# chess.net
KiCad netlist of a schematic drawn in EAGLE
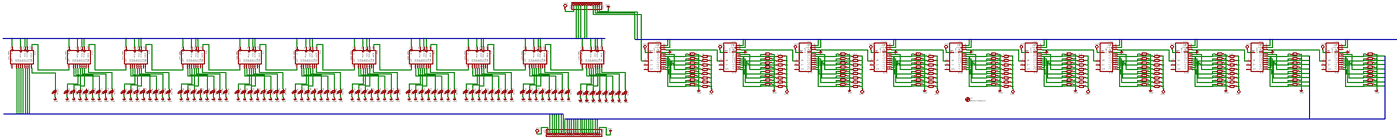
[diagram p0: schematic, sheet 1, overview]
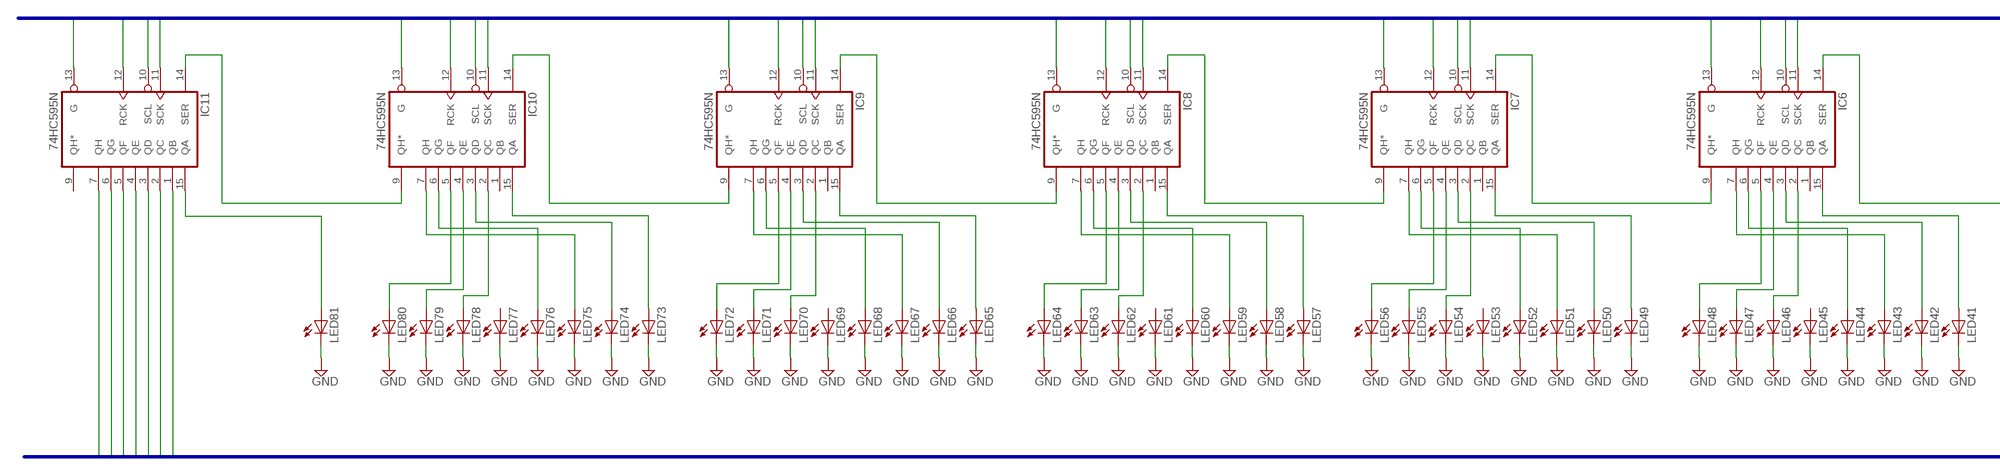
[diagram p1: schematic, sheet 1, part 1 of 4]
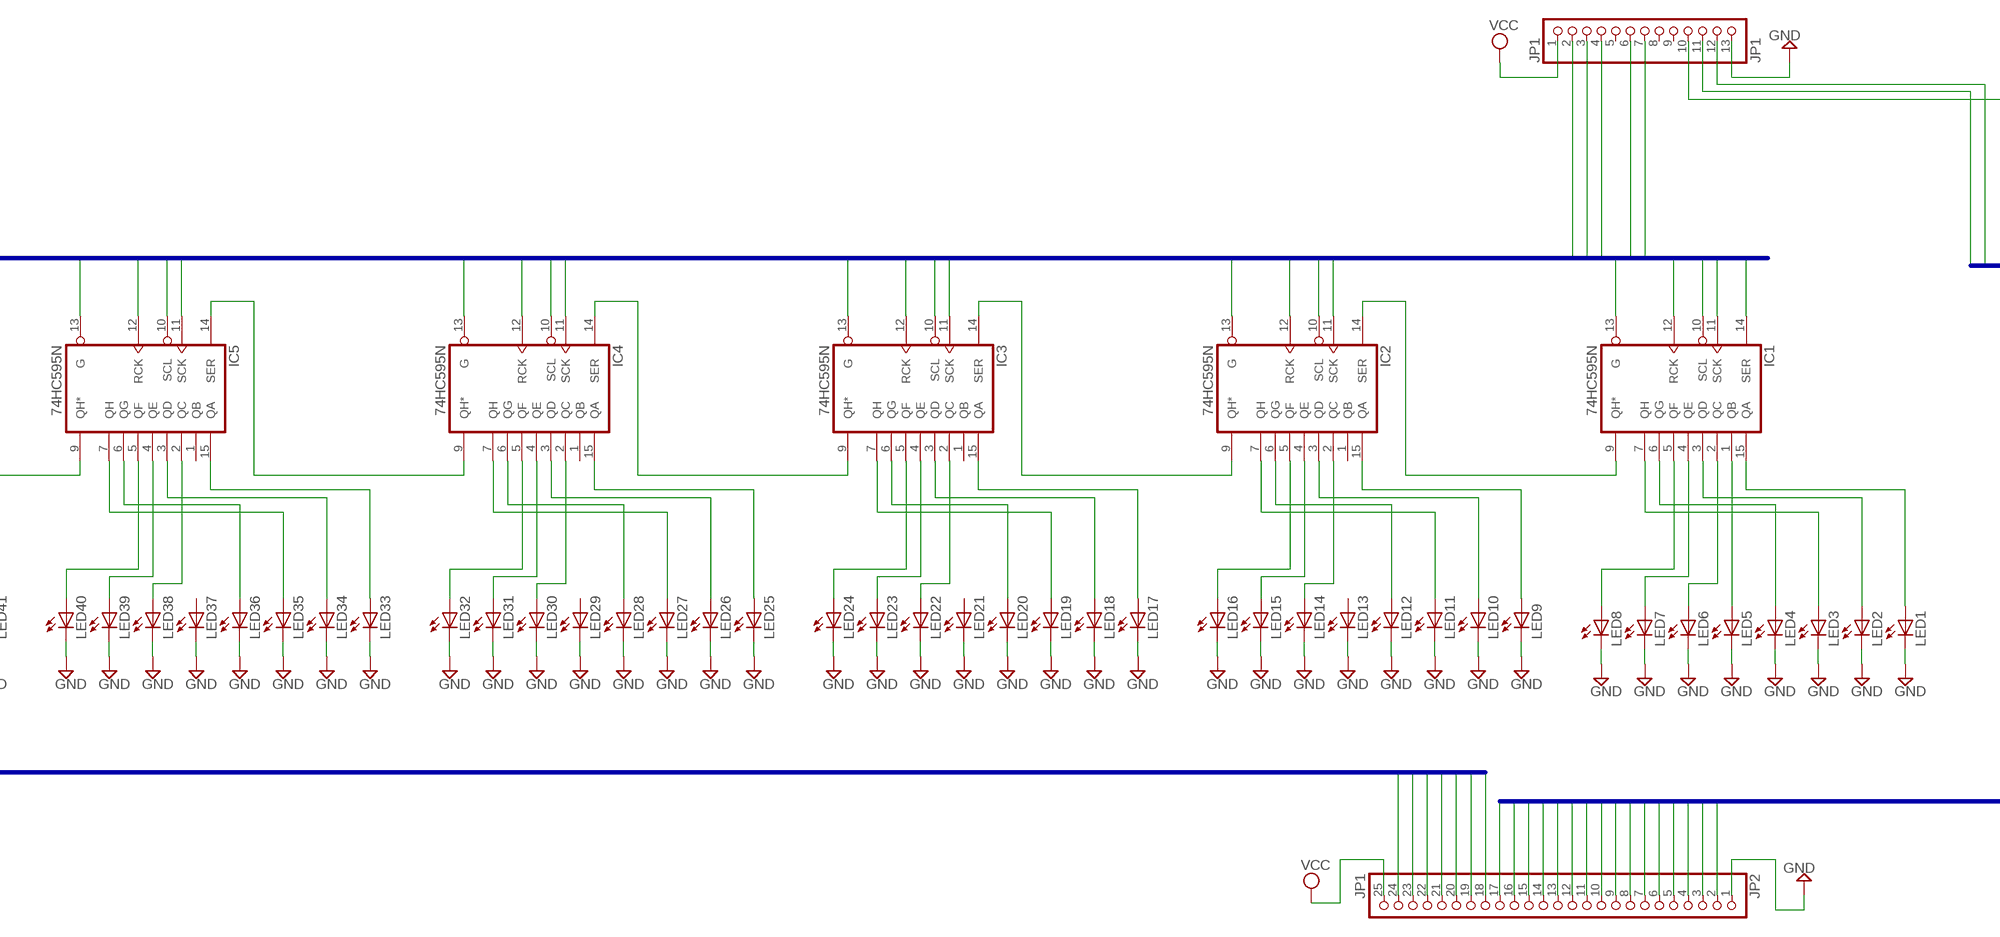
[diagram p2: schematic, sheet 1, part 2 of 4]
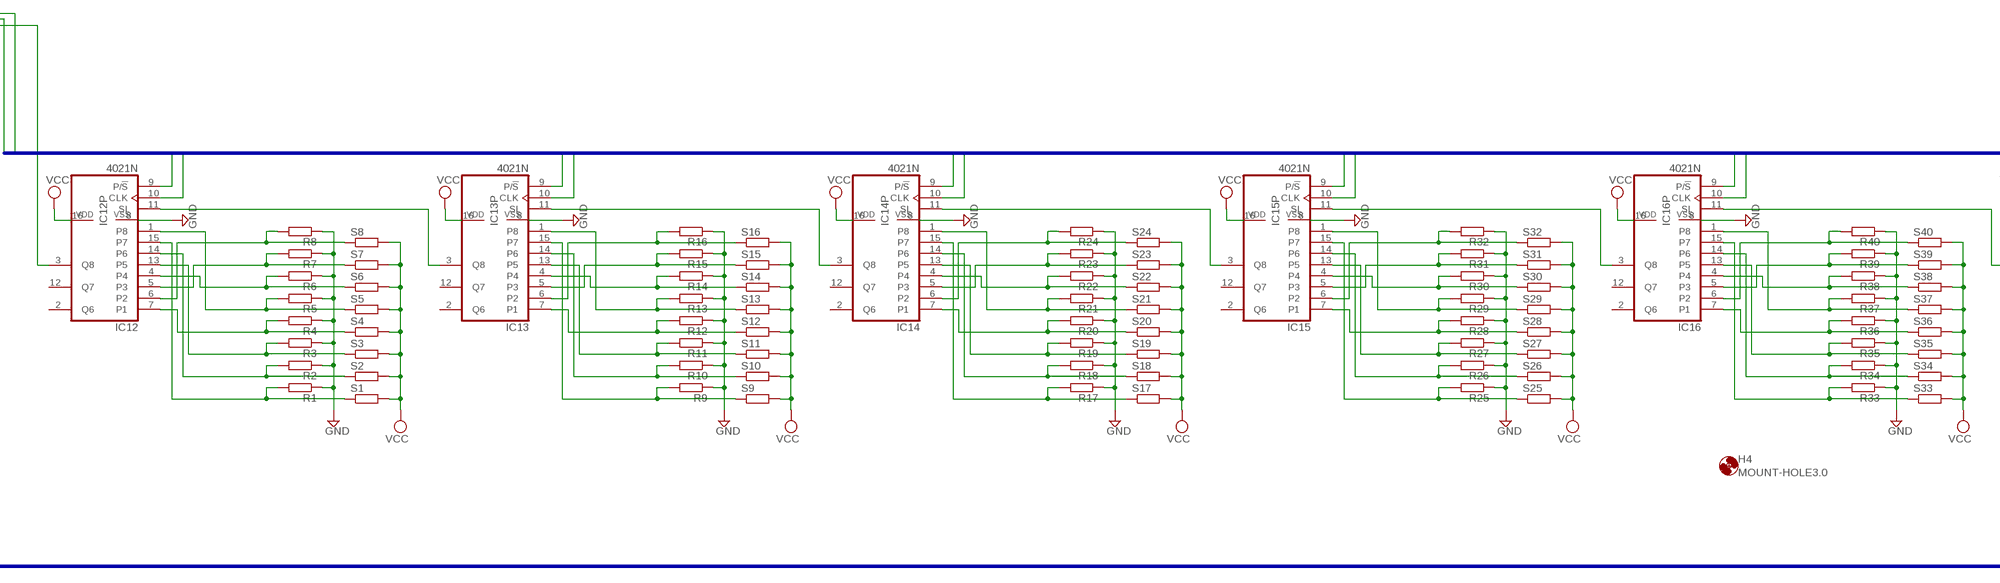
[diagram p3: schematic, sheet 1, part 3 of 4]
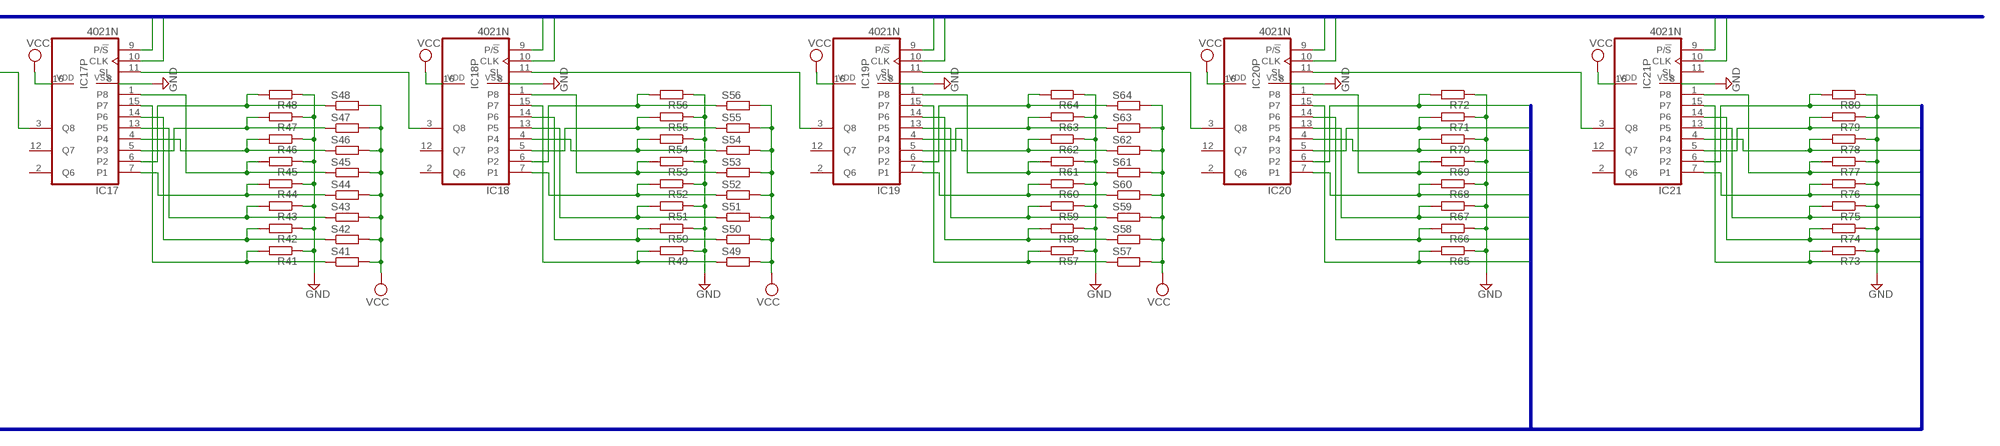
[diagram p4: schematic, sheet 1, part 4 of 4]

(export (version "E")
  (design (tool "Eeschema 10.0.6"))
  (components
    (comp (ref "H4")
      (value "MOUNT-HOLE3.0")
      (footprint "eagle-import:3,0")
      (libsource (lib "eagle-import") (part "MOUNT-HOLE3.0"))
    )
    (comp (ref "IC1")
      (value "74HC595N")
      (footprint "eagle-import:DIL16")
      (libsource (lib "eagle-import") (part "74595NHC"))
    )
    (comp (ref "IC2")
      (value "74HC595N")
      (footprint "eagle-import:DIL16")
      (libsource (lib "eagle-import") (part "74595NHC"))
    )
    (comp (ref "IC3")
      (value "74HC595N")
      (footprint "eagle-import:DIL16")
      (libsource (lib "eagle-import") (part "74595NHC"))
    )
    (comp (ref "IC4")
      (value "74HC595N")
      (footprint "eagle-import:DIL16")
      (libsource (lib "eagle-import") (part "74595NHC"))
    )
    (comp (ref "IC5")
      (value "74HC595N")
      (footprint "eagle-import:DIL16")
      (libsource (lib "eagle-import") (part "74595NHC"))
    )
    (comp (ref "IC6")
      (value "74HC595N")
      (footprint "eagle-import:DIL16")
      (libsource (lib "eagle-import") (part "74595NHC"))
    )
    (comp (ref "IC7")
      (value "74HC595N")
      (footprint "eagle-import:DIL16")
      (libsource (lib "eagle-import") (part "74595NHC"))
    )
    (comp (ref "IC8")
      (value "74HC595N")
      (footprint "eagle-import:DIL16")
      (libsource (lib "eagle-import") (part "74595NHC"))
    )
    (comp (ref "IC9")
      (value "74HC595N")
      (footprint "eagle-import:DIL16")
      (libsource (lib "eagle-import") (part "74595NHC"))
    )
    (comp (ref "IC10")
      (value "74HC595N")
      (footprint "eagle-import:DIL16")
      (libsource (lib "eagle-import") (part "74595NHC"))
    )
    (comp (ref "IC11")
      (value "74HC595N")
      (footprint "eagle-import:DIL16")
      (libsource (lib "eagle-import") (part "74595NHC"))
    )
    (comp (ref "IC12")
      (value "4021N")
      (footprint "eagle-import:DIL16")
      (libsource (lib "eagle-import") (part "4021N"))
    )
    (comp (ref "IC13")
      (value "4021N")
      (footprint "eagle-import:DIL16")
      (libsource (lib "eagle-import") (part "4021N"))
    )
    (comp (ref "IC14")
      (value "4021N")
      (footprint "eagle-import:DIL16")
      (libsource (lib "eagle-import") (part "4021N"))
    )
    (comp (ref "IC15")
      (value "4021N")
      (footprint "eagle-import:DIL16")
      (libsource (lib "eagle-import") (part "4021N"))
    )
    (comp (ref "IC16")
      (value "4021N")
      (footprint "eagle-import:DIL16")
      (libsource (lib "eagle-import") (part "4021N"))
    )
    (comp (ref "IC17")
      (value "4021N")
      (footprint "eagle-import:DIL16")
      (libsource (lib "eagle-import") (part "4021N"))
    )
    (comp (ref "IC18")
      (value "4021N")
      (footprint "eagle-import:DIL16")
      (libsource (lib "eagle-import") (part "4021N"))
    )
    (comp (ref "IC19")
      (value "4021N")
      (footprint "eagle-import:DIL16")
      (libsource (lib "eagle-import") (part "4021N"))
    )
    (comp (ref "IC20")
      (value "4021N")
      (footprint "eagle-import:DIL16")
      (libsource (lib "eagle-import") (part "4021N"))
    )
    (comp (ref "IC21")
      (value "4021N")
      (footprint "eagle-import:DIL16")
      (libsource (lib "eagle-import") (part "4021N"))
    )
    (comp (ref "JP1")
      (value "JP1")
      (footprint "eagle-import:1X13")
      (libsource (lib "eagle-import") (part "PINHD-1X13"))
    )
    (comp (ref "JP2")
      (value "JP1")
      (footprint "eagle-import:1X25")
      (libsource (lib "eagle-import") (part "PINHD-1X25"))
    )
    (comp (ref "LED1")
      (value "LED5MM")
      (footprint "eagle-import:LED5MM")
      (libsource (lib "eagle-import") (part "LED5MM"))
    )
    (comp (ref "LED2")
      (value "LED5MM")
      (footprint "eagle-import:LED5MM")
      (libsource (lib "eagle-import") (part "LED5MM"))
    )
    (comp (ref "LED3")
      (value "LED5MM")
      (footprint "eagle-import:LED5MM")
      (libsource (lib "eagle-import") (part "LED5MM"))
    )
    (comp (ref "LED4")
      (value "LED5MM")
      (footprint "eagle-import:LED5MM")
      (libsource (lib "eagle-import") (part "LED5MM"))
    )
    (comp (ref "LED5")
      (value "LED5MM")
      (footprint "eagle-import:LED5MM")
      (libsource (lib "eagle-import") (part "LED5MM"))
    )
    (comp (ref "LED6")
      (value "LED5MM")
      (footprint "eagle-import:LED5MM")
      (libsource (lib "eagle-import") (part "LED5MM"))
    )
    (comp (ref "LED7")
      (value "LED5MM")
      (footprint "eagle-import:LED5MM")
      (libsource (lib "eagle-import") (part "LED5MM"))
    )
    (comp (ref "LED8")
      (value "LED5MM")
      (footprint "eagle-import:LED5MM")
      (libsource (lib "eagle-import") (part "LED5MM"))
    )
    (comp (ref "LED9")
      (value "LED5MM")
      (footprint "eagle-import:LED5MM")
      (libsource (lib "eagle-import") (part "LED5MM"))
    )
    (comp (ref "LED10")
      (value "LED5MM")
      (footprint "eagle-import:LED5MM")
      (libsource (lib "eagle-import") (part "LED5MM"))
    )
    (comp (ref "LED11")
      (value "LED5MM")
      (footprint "eagle-import:LED5MM")
      (libsource (lib "eagle-import") (part "LED5MM"))
    )
    (comp (ref "LED12")
      (value "LED5MM")
      (footprint "eagle-import:LED5MM")
      (libsource (lib "eagle-import") (part "LED5MM"))
    )
    (comp (ref "LED13")
      (value "LED5MM")
      (footprint "eagle-import:LED5MM")
      (libsource (lib "eagle-import") (part "LED5MM"))
    )
    (comp (ref "LED14")
      (value "LED5MM")
      (footprint "eagle-import:LED5MM")
      (libsource (lib "eagle-import") (part "LED5MM"))
    )
    (comp (ref "LED15")
      (value "LED5MM")
      (footprint "eagle-import:LED5MM")
      (libsource (lib "eagle-import") (part "LED5MM"))
    )
    (comp (ref "LED16")
      (value "LED5MM")
      (footprint "eagle-import:LED5MM")
      (libsource (lib "eagle-import") (part "LED5MM"))
    )
    (comp (ref "LED17")
      (value "LED5MM")
      (footprint "eagle-import:LED5MM")
      (libsource (lib "eagle-import") (part "LED5MM"))
    )
    (comp (ref "LED18")
      (value "LED5MM")
      (footprint "eagle-import:LED5MM")
      (libsource (lib "eagle-import") (part "LED5MM"))
    )
    (comp (ref "LED19")
      (value "LED5MM")
      (footprint "eagle-import:LED5MM")
      (libsource (lib "eagle-import") (part "LED5MM"))
    )
    (comp (ref "LED20")
      (value "LED5MM")
      (footprint "eagle-import:LED5MM")
      (libsource (lib "eagle-import") (part "LED5MM"))
    )
    (comp (ref "LED21")
      (value "LED5MM")
      (footprint "eagle-import:LED5MM")
      (libsource (lib "eagle-import") (part "LED5MM"))
    )
    (comp (ref "LED22")
      (value "LED5MM")
      (footprint "eagle-import:LED5MM")
      (libsource (lib "eagle-import") (part "LED5MM"))
    )
    (comp (ref "LED23")
      (value "LED5MM")
      (footprint "eagle-import:LED5MM")
      (libsource (lib "eagle-import") (part "LED5MM"))
    )
    (comp (ref "LED24")
      (value "LED5MM")
      (footprint "eagle-import:LED5MM")
      (libsource (lib "eagle-import") (part "LED5MM"))
    )
    (comp (ref "LED25")
      (value "LED5MM")
      (footprint "eagle-import:LED5MM")
      (libsource (lib "eagle-import") (part "LED5MM"))
    )
    (comp (ref "LED26")
      (value "LED5MM")
      (footprint "eagle-import:LED5MM")
      (libsource (lib "eagle-import") (part "LED5MM"))
    )
    (comp (ref "LED27")
      (value "LED5MM")
      (footprint "eagle-import:LED5MM")
      (libsource (lib "eagle-import") (part "LED5MM"))
    )
    (comp (ref "LED28")
      (value "LED5MM")
      (footprint "eagle-import:LED5MM")
      (libsource (lib "eagle-import") (part "LED5MM"))
    )
    (comp (ref "LED29")
      (value "LED5MM")
      (footprint "eagle-import:LED5MM")
      (libsource (lib "eagle-import") (part "LED5MM"))
    )
    (comp (ref "LED30")
      (value "LED5MM")
      (footprint "eagle-import:LED5MM")
      (libsource (lib "eagle-import") (part "LED5MM"))
    )
    (comp (ref "LED31")
      (value "LED5MM")
      (footprint "eagle-import:LED5MM")
      (libsource (lib "eagle-import") (part "LED5MM"))
    )
    (comp (ref "LED32")
      (value "LED5MM")
      (footprint "eagle-import:LED5MM")
      (libsource (lib "eagle-import") (part "LED5MM"))
    )
    (comp (ref "LED33")
      (value "LED5MM")
      (footprint "eagle-import:LED5MM")
      (libsource (lib "eagle-import") (part "LED5MM"))
    )
    (comp (ref "LED34")
      (value "LED5MM")
      (footprint "eagle-import:LED5MM")
      (libsource (lib "eagle-import") (part "LED5MM"))
    )
    (comp (ref "LED35")
      (value "LED5MM")
      (footprint "eagle-import:LED5MM")
      (libsource (lib "eagle-import") (part "LED5MM"))
    )
    (comp (ref "LED36")
      (value "LED5MM")
      (footprint "eagle-import:LED5MM")
      (libsource (lib "eagle-import") (part "LED5MM"))
    )
    (comp (ref "LED37")
      (value "LED5MM")
      (footprint "eagle-import:LED5MM")
      (libsource (lib "eagle-import") (part "LED5MM"))
    )
    (comp (ref "LED38")
      (value "LED5MM")
      (footprint "eagle-import:LED5MM")
      (libsource (lib "eagle-import") (part "LED5MM"))
    )
    (comp (ref "LED39")
      (value "LED5MM")
      (footprint "eagle-import:LED5MM")
      (libsource (lib "eagle-import") (part "LED5MM"))
    )
    (comp (ref "LED40")
      (value "LED5MM")
      (footprint "eagle-import:LED5MM")
      (libsource (lib "eagle-import") (part "LED5MM"))
    )
    (comp (ref "LED41")
      (value "LED5MM")
      (footprint "eagle-import:LED5MM")
      (libsource (lib "eagle-import") (part "LED5MM"))
    )
    (comp (ref "LED42")
      (value "LED5MM")
      (footprint "eagle-import:LED5MM")
      (libsource (lib "eagle-import") (part "LED5MM"))
    )
    (comp (ref "LED43")
      (value "LED5MM")
      (footprint "eagle-import:LED5MM")
      (libsource (lib "eagle-import") (part "LED5MM"))
    )
    (comp (ref "LED44")
      (value "LED5MM")
      (footprint "eagle-import:LED5MM")
      (libsource (lib "eagle-import") (part "LED5MM"))
    )
    (comp (ref "LED45")
      (value "LED5MM")
      (footprint "eagle-import:LED5MM")
      (libsource (lib "eagle-import") (part "LED5MM"))
    )
    (comp (ref "LED46")
      (value "LED5MM")
      (footprint "eagle-import:LED5MM")
      (libsource (lib "eagle-import") (part "LED5MM"))
    )
    (comp (ref "LED47")
      (value "LED5MM")
      (footprint "eagle-import:LED5MM")
      (libsource (lib "eagle-import") (part "LED5MM"))
    )
    (comp (ref "LED48")
      (value "LED5MM")
      (footprint "eagle-import:LED5MM")
      (libsource (lib "eagle-import") (part "LED5MM"))
    )
    (comp (ref "LED49")
      (value "LED5MM")
      (footprint "eagle-import:LED5MM")
      (libsource (lib "eagle-import") (part "LED5MM"))
    )
    (comp (ref "LED50")
      (value "LED5MM")
      (footprint "eagle-import:LED5MM")
      (libsource (lib "eagle-import") (part "LED5MM"))
    )
    (comp (ref "LED51")
      (value "LED5MM")
      (footprint "eagle-import:LED5MM")
      (libsource (lib "eagle-import") (part "LED5MM"))
    )
    (comp (ref "LED52")
      (value "LED5MM")
      (footprint "eagle-import:LED5MM")
      (libsource (lib "eagle-import") (part "LED5MM"))
    )
    (comp (ref "LED53")
      (value "LED5MM")
      (footprint "eagle-import:LED5MM")
      (libsource (lib "eagle-import") (part "LED5MM"))
    )
    (comp (ref "LED54")
      (value "LED5MM")
      (footprint "eagle-import:LED5MM")
      (libsource (lib "eagle-import") (part "LED5MM"))
    )
    (comp (ref "LED55")
      (value "LED5MM")
      (footprint "eagle-import:LED5MM")
      (libsource (lib "eagle-import") (part "LED5MM"))
    )
    (comp (ref "LED56")
      (value "LED5MM")
      (footprint "eagle-import:LED5MM")
      (libsource (lib "eagle-import") (part "LED5MM"))
    )
    (comp (ref "LED57")
      (value "LED5MM")
      (footprint "eagle-import:LED5MM")
      (libsource (lib "eagle-import") (part "LED5MM"))
    )
    (comp (ref "LED58")
      (value "LED5MM")
      (footprint "eagle-import:LED5MM")
      (libsource (lib "eagle-import") (part "LED5MM"))
    )
    (comp (ref "LED59")
      (value "LED5MM")
      (footprint "eagle-import:LED5MM")
      (libsource (lib "eagle-import") (part "LED5MM"))
    )
    (comp (ref "LED60")
      (value "LED5MM")
      (footprint "eagle-import:LED5MM")
      (libsource (lib "eagle-import") (part "LED5MM"))
    )
    (comp (ref "LED61")
      (value "LED5MM")
      (footprint "eagle-import:LED5MM")
      (libsource (lib "eagle-import") (part "LED5MM"))
    )
    (comp (ref "LED62")
      (value "LED5MM")
      (footprint "eagle-import:LED5MM")
      (libsource (lib "eagle-import") (part "LED5MM"))
    )
    (comp (ref "LED63")
      (value "LED5MM")
      (footprint "eagle-import:LED5MM")
      (libsource (lib "eagle-import") (part "LED5MM"))
    )
    (comp (ref "LED64")
      (value "LED5MM")
      (footprint "eagle-import:LED5MM")
      (libsource (lib "eagle-import") (part "LED5MM"))
    )
    (comp (ref "LED65")
      (value "LED5MM")
      (footprint "eagle-import:LED5MM")
      (libsource (lib "eagle-import") (part "LED5MM"))
    )
    (comp (ref "LED66")
      (value "LED5MM")
      (footprint "eagle-import:LED5MM")
      (libsource (lib "eagle-import") (part "LED5MM"))
    )
    (comp (ref "LED67")
      (value "LED5MM")
      (footprint "eagle-import:LED5MM")
      (libsource (lib "eagle-import") (part "LED5MM"))
    )
    (comp (ref "LED68")
      (value "LED5MM")
      (footprint "eagle-import:LED5MM")
      (libsource (lib "eagle-import") (part "LED5MM"))
    )
    (comp (ref "LED69")
      (value "LED5MM")
      (footprint "eagle-import:LED5MM")
      (libsource (lib "eagle-import") (part "LED5MM"))
    )
    (comp (ref "LED70")
      (value "LED5MM")
      (footprint "eagle-import:LED5MM")
      (libsource (lib "eagle-import") (part "LED5MM"))
    )
    (comp (ref "LED71")
      (value "LED5MM")
      (footprint "eagle-import:LED5MM")
      (libsource (lib "eagle-import") (part "LED5MM"))
    )
    (comp (ref "LED72")
      (value "LED5MM")
      (footprint "eagle-import:LED5MM")
      (libsource (lib "eagle-import") (part "LED5MM"))
    )
    (comp (ref "LED73")
      (value "LED5MM")
      (footprint "eagle-import:LED5MM")
      (libsource (lib "eagle-import") (part "LED5MM"))
    )
    (comp (ref "LED74")
      (value "LED5MM")
      (footprint "eagle-import:LED5MM")
      (libsource (lib "eagle-import") (part "LED5MM"))
    )
    (comp (ref "LED75")
      (value "LED5MM")
      (footprint "eagle-import:LED5MM")
      (libsource (lib "eagle-import") (part "LED5MM"))
    )
    (comp (ref "LED76")
      (value "LED5MM")
      (footprint "eagle-import:LED5MM")
      (libsource (lib "eagle-import") (part "LED5MM"))
    )
    (comp (ref "LED77")
      (value "LED5MM")
      (footprint "eagle-import:LED5MM")
      (libsource (lib "eagle-import") (part "LED5MM"))
    )
    (comp (ref "LED78")
      (value "LED5MM")
      (footprint "eagle-import:LED5MM")
      (libsource (lib "eagle-import") (part "LED5MM"))
    )
    (comp (ref "LED79")
      (value "LED5MM")
      (footprint "eagle-import:LED5MM")
      (libsource (lib "eagle-import") (part "LED5MM"))
    )
    (comp (ref "LED80")
      (value "LED5MM")
      (footprint "eagle-import:LED5MM")
      (libsource (lib "eagle-import") (part "LED5MM"))
    )
    (comp (ref "LED81")
      (value "LED5MM")
      (footprint "eagle-import:LED5MM")
      (libsource (lib "eagle-import") (part "LED5MM"))
    )
    (comp (ref "R1")
      (value "R-EU_0207/15")
      (footprint "eagle-import:0207_15")
      (libsource (lib "eagle-import") (part "R-EU_0207/15"))
    )
    (comp (ref "R2")
      (value "R-EU_0207/15")
      (footprint "eagle-import:0207_15")
      (libsource (lib "eagle-import") (part "R-EU_0207/15"))
    )
    (comp (ref "R3")
      (value "R-EU_0207/15")
      (footprint "eagle-import:0207_15")
      (libsource (lib "eagle-import") (part "R-EU_0207/15"))
    )
    (comp (ref "R4")
      (value "R-EU_0207/15")
      (footprint "eagle-import:0207_15")
      (libsource (lib "eagle-import") (part "R-EU_0207/15"))
    )
    (comp (ref "R5")
      (value "R-EU_0207/15")
      (footprint "eagle-import:0207_15")
      (libsource (lib "eagle-import") (part "R-EU_0207/15"))
    )
    (comp (ref "R6")
      (value "R-EU_0207/15")
      (footprint "eagle-import:0207_15")
      (libsource (lib "eagle-import") (part "R-EU_0207/15"))
    )
    (comp (ref "R7")
      (value "R-EU_0207/15")
      (footprint "eagle-import:0207_15")
      (libsource (lib "eagle-import") (part "R-EU_0207/15"))
    )
    (comp (ref "R8")
      (value "R-EU_0207/15")
      (footprint "eagle-import:0207_15")
      (libsource (lib "eagle-import") (part "R-EU_0207/15"))
    )
    (comp (ref "R9")
      (value "R-EU_0207/15")
      (footprint "eagle-import:0207_15")
      (libsource (lib "eagle-import") (part "R-EU_0207/15"))
    )
    (comp (ref "R10")
      (value "R-EU_0207/15")
      (footprint "eagle-import:0207_15")
      (libsource (lib "eagle-import") (part "R-EU_0207/15"))
    )
    (comp (ref "R11")
      (value "R-EU_0207/15")
      (footprint "eagle-import:0207_15")
      (libsource (lib "eagle-import") (part "R-EU_0207/15"))
    )
    (comp (ref "R12")
      (value "R-EU_0207/15")
      (footprint "eagle-import:0207_15")
      (libsource (lib "eagle-import") (part "R-EU_0207/15"))
    )
    (comp (ref "R13")
      (value "R-EU_0207/15")
      (footprint "eagle-import:0207_15")
      (libsource (lib "eagle-import") (part "R-EU_0207/15"))
    )
    (comp (ref "R14")
      (value "R-EU_0207/15")
      (footprint "eagle-import:0207_15")
      (libsource (lib "eagle-import") (part "R-EU_0207/15"))
    )
    (comp (ref "R15")
      (value "R-EU_0207/15")
      (footprint "eagle-import:0207_15")
      (libsource (lib "eagle-import") (part "R-EU_0207/15"))
    )
    (comp (ref "R16")
      (value "R-EU_0207/15")
      (footprint "eagle-import:0207_15")
      (libsource (lib "eagle-import") (part "R-EU_0207/15"))
    )
    (comp (ref "R17")
      (value "R-EU_0207/15")
      (footprint "eagle-import:0207_15")
      (libsource (lib "eagle-import") (part "R-EU_0207/15"))
    )
    (comp (ref "R18")
      (value "R-EU_0207/15")
      (footprint "eagle-import:0207_15")
      (libsource (lib "eagle-import") (part "R-EU_0207/15"))
    )
    (comp (ref "R19")
      (value "R-EU_0207/15")
      (footprint "eagle-import:0207_15")
      (libsource (lib "eagle-import") (part "R-EU_0207/15"))
    )
    (comp (ref "R20")
      (value "R-EU_0207/15")
      (footprint "eagle-import:0207_15")
      (libsource (lib "eagle-import") (part "R-EU_0207/15"))
    )
    (comp (ref "R21")
      (value "R-EU_0207/15")
      (footprint "eagle-import:0207_15")
      (libsource (lib "eagle-import") (part "R-EU_0207/15"))
    )
    (comp (ref "R22")
      (value "R-EU_0207/15")
      (footprint "eagle-import:0207_15")
      (libsource (lib "eagle-import") (part "R-EU_0207/15"))
    )
    (comp (ref "R23")
      (value "R-EU_0207/15")
      (footprint "eagle-import:0207_15")
      (libsource (lib "eagle-import") (part "R-EU_0207/15"))
    )
    (comp (ref "R24")
      (value "R-EU_0207/15")
      (footprint "eagle-import:0207_15")
      (libsource (lib "eagle-import") (part "R-EU_0207/15"))
    )
    (comp (ref "R25")
      (value "R-EU_0207/15")
      (footprint "eagle-import:0207_15")
      (libsource (lib "eagle-import") (part "R-EU_0207/15"))
    )
    (comp (ref "R26")
      (value "R-EU_0207/15")
      (footprint "eagle-import:0207_15")
      (libsource (lib "eagle-import") (part "R-EU_0207/15"))
    )
    (comp (ref "R27")
      (value "R-EU_0207/15")
      (footprint "eagle-import:0207_15")
      (libsource (lib "eagle-import") (part "R-EU_0207/15"))
    )
    (comp (ref "R28")
      (value "R-EU_0207/15")
      (footprint "eagle-import:0207_15")
      (libsource (lib "eagle-import") (part "R-EU_0207/15"))
    )
    (comp (ref "R29")
      (value "R-EU_0207/15")
      (footprint "eagle-import:0207_15")
      (libsource (lib "eagle-import") (part "R-EU_0207/15"))
    )
    (comp (ref "R30")
      (value "R-EU_0207/15")
      (footprint "eagle-import:0207_15")
      (libsource (lib "eagle-import") (part "R-EU_0207/15"))
    )
    (comp (ref "R31")
      (value "R-EU_0207/15")
      (footprint "eagle-import:0207_15")
      (libsource (lib "eagle-import") (part "R-EU_0207/15"))
    )
    (comp (ref "R32")
      (value "R-EU_0207/15")
      (footprint "eagle-import:0207_15")
      (libsource (lib "eagle-import") (part "R-EU_0207/15"))
    )
    (comp (ref "R33")
      (value "R-EU_0207/15")
      (footprint "eagle-import:0207_15")
      (libsource (lib "eagle-import") (part "R-EU_0207/15"))
    )
    (comp (ref "R34")
      (value "R-EU_0207/15")
      (footprint "eagle-import:0207_15")
      (libsource (lib "eagle-import") (part "R-EU_0207/15"))
    )
    (comp (ref "R35")
      (value "R-EU_0207/15")
      (footprint "eagle-import:0207_15")
      (libsource (lib "eagle-import") (part "R-EU_0207/15"))
    )
    (comp (ref "R36")
      (value "R-EU_0207/15")
      (footprint "eagle-import:0207_15")
      (libsource (lib "eagle-import") (part "R-EU_0207/15"))
    )
    (comp (ref "R37")
      (value "R-EU_0207/15")
      (footprint "eagle-import:0207_15")
      (libsource (lib "eagle-import") (part "R-EU_0207/15"))
    )
    (comp (ref "R38")
      (value "R-EU_0207/15")
      (footprint "eagle-import:0207_15")
      (libsource (lib "eagle-import") (part "R-EU_0207/15"))
    )
    (comp (ref "R39")
      (value "R-EU_0207/15")
      (footprint "eagle-import:0207_15")
      (libsource (lib "eagle-import") (part "R-EU_0207/15"))
    )
    (comp (ref "R40")
      (value "R-EU_0207/15")
      (footprint "eagle-import:0207_15")
      (libsource (lib "eagle-import") (part "R-EU_0207/15"))
    )
    (comp (ref "R41")
      (value "R-EU_0207/15")
      (footprint "eagle-import:0207_15")
      (libsource (lib "eagle-import") (part "R-EU_0207/15"))
    )
    (comp (ref "R42")
      (value "R-EU_0207/15")
      (footprint "eagle-import:0207_15")
      (libsource (lib "eagle-import") (part "R-EU_0207/15"))
    )
    (comp (ref "R43")
      (value "R-EU_0207/15")
      (footprint "eagle-import:0207_15")
      (libsource (lib "eagle-import") (part "R-EU_0207/15"))
    )
    (comp (ref "R44")
      (value "R-EU_0207/15")
      (footprint "eagle-import:0207_15")
      (libsource (lib "eagle-import") (part "R-EU_0207/15"))
    )
    (comp (ref "R45")
      (value "R-EU_0207/15")
      (footprint "eagle-import:0207_15")
      (libsource (lib "eagle-import") (part "R-EU_0207/15"))
    )
    (comp (ref "R46")
      (value "R-EU_0207/15")
      (footprint "eagle-import:0207_15")
      (libsource (lib "eagle-import") (part "R-EU_0207/15"))
    )
    (comp (ref "R47")
      (value "R-EU_0207/15")
      (footprint "eagle-import:0207_15")
      (libsource (lib "eagle-import") (part "R-EU_0207/15"))
    )
    (comp (ref "R48")
      (value "R-EU_0207/15")
      (footprint "eagle-import:0207_15")
      (libsource (lib "eagle-import") (part "R-EU_0207/15"))
    )
    (comp (ref "R49")
      (value "R-EU_0207/15")
      (footprint "eagle-import:0207_15")
      (libsource (lib "eagle-import") (part "R-EU_0207/15"))
    )
    (comp (ref "R50")
      (value "R-EU_0207/15")
      (footprint "eagle-import:0207_15")
      (libsource (lib "eagle-import") (part "R-EU_0207/15"))
    )
    (comp (ref "R51")
      (value "R-EU_0207/15")
      (footprint "eagle-import:0207_15")
      (libsource (lib "eagle-import") (part "R-EU_0207/15"))
    )
    (comp (ref "R52")
      (value "R-EU_0207/15")
      (footprint "eagle-import:0207_15")
      (libsource (lib "eagle-import") (part "R-EU_0207/15"))
    )
    (comp (ref "R53")
      (value "R-EU_0207/15")
      (footprint "eagle-import:0207_15")
      (libsource (lib "eagle-import") (part "R-EU_0207/15"))
    )
    (comp (ref "R54")
      (value "R-EU_0207/15")
      (footprint "eagle-import:0207_15")
      (libsource (lib "eagle-import") (part "R-EU_0207/15"))
    )
    (comp (ref "R55")
      (value "R-EU_0207/15")
      (footprint "eagle-import:0207_15")
      (libsource (lib "eagle-import") (part "R-EU_0207/15"))
    )
    (comp (ref "R56")
      (value "R-EU_0207/15")
      (footprint "eagle-import:0207_15")
      (libsource (lib "eagle-import") (part "R-EU_0207/15"))
    )
    (comp (ref "R57")
      (value "R-EU_0207/15")
      (footprint "eagle-import:0207_15")
      (libsource (lib "eagle-import") (part "R-EU_0207/15"))
    )
    (comp (ref "R58")
      (value "R-EU_0207/15")
      (footprint "eagle-import:0207_15")
      (libsource (lib "eagle-import") (part "R-EU_0207/15"))
    )
    (comp (ref "R59")
      (value "R-EU_0207/15")
      (footprint "eagle-import:0207_15")
      (libsource (lib "eagle-import") (part "R-EU_0207/15"))
    )
    (comp (ref "R60")
      (value "R-EU_0207/15")
      (footprint "eagle-import:0207_15")
      (libsource (lib "eagle-import") (part "R-EU_0207/15"))
    )
    (comp (ref "R61")
      (value "R-EU_0207/15")
      (footprint "eagle-import:0207_15")
      (libsource (lib "eagle-import") (part "R-EU_0207/15"))
    )
    (comp (ref "R62")
      (value "R-EU_0207/15")
      (footprint "eagle-import:0207_15")
      (libsource (lib "eagle-import") (part "R-EU_0207/15"))
    )
    (comp (ref "R63")
      (value "R-EU_0207/15")
      (footprint "eagle-import:0207_15")
      (libsource (lib "eagle-import") (part "R-EU_0207/15"))
    )
    (comp (ref "R64")
      (value "R-EU_0207/15")
      (footprint "eagle-import:0207_15")
      (libsource (lib "eagle-import") (part "R-EU_0207/15"))
    )
    (comp (ref "R65")
      (value "R-EU_0207/15")
      (footprint "eagle-import:0207_15")
      (libsource (lib "eagle-import") (part "R-EU_0207/15"))
    )
    (comp (ref "R66")
      (value "R-EU_0207/15")
      (footprint "eagle-import:0207_15")
      (libsource (lib "eagle-import") (part "R-EU_0207/15"))
    )
    (comp (ref "R67")
      (value "R-EU_0207/15")
      (footprint "eagle-import:0207_15")
      (libsource (lib "eagle-import") (part "R-EU_0207/15"))
    )
    (comp (ref "R68")
      (value "R-EU_0207/15")
      (footprint "eagle-import:0207_15")
      (libsource (lib "eagle-import") (part "R-EU_0207/15"))
    )
    (comp (ref "R69")
      (value "R-EU_0207/15")
      (footprint "eagle-import:0207_15")
      (libsource (lib "eagle-import") (part "R-EU_0207/15"))
    )
    (comp (ref "R70")
      (value "R-EU_0207/15")
      (footprint "eagle-import:0207_15")
      (libsource (lib "eagle-import") (part "R-EU_0207/15"))
    )
    (comp (ref "R71")
      (value "R-EU_0207/15")
      (footprint "eagle-import:0207_15")
      (libsource (lib "eagle-import") (part "R-EU_0207/15"))
    )
    (comp (ref "R72")
      (value "R-EU_0207/15")
      (footprint "eagle-import:0207_15")
      (libsource (lib "eagle-import") (part "R-EU_0207/15"))
    )
    (comp (ref "R73")
      (value "R-EU_0207/15")
      (footprint "eagle-import:0207_15")
      (libsource (lib "eagle-import") (part "R-EU_0207/15"))
    )
    (comp (ref "R74")
      (value "R-EU_0207/15")
      (footprint "eagle-import:0207_15")
      (libsource (lib "eagle-import") (part "R-EU_0207/15"))
    )
    (comp (ref "R75")
      (value "R-EU_0207/15")
      (footprint "eagle-import:0207_15")
      (libsource (lib "eagle-import") (part "R-EU_0207/15"))
    )
    (comp (ref "R76")
      (value "R-EU_0207/15")
      (footprint "eagle-import:0207_15")
      (libsource (lib "eagle-import") (part "R-EU_0207/15"))
    )
    (comp (ref "R77")
      (value "R-EU_0207/15")
      (footprint "eagle-import:0207_15")
      (libsource (lib "eagle-import") (part "R-EU_0207/15"))
    )
    (comp (ref "R78")
      (value "R-EU_0207/15")
      (footprint "eagle-import:0207_15")
      (libsource (lib "eagle-import") (part "R-EU_0207/15"))
    )
    (comp (ref "R79")
      (value "R-EU_0207/15")
      (footprint "eagle-import:0207_15")
      (libsource (lib "eagle-import") (part "R-EU_0207/15"))
    )
    (comp (ref "R80")
      (value "R-EU_0207/15")
      (footprint "eagle-import:0207_15")
      (libsource (lib "eagle-import") (part "R-EU_0207/15"))
    )
    (comp (ref "S1")
      (value "R-EU_0617/22")
      (footprint "eagle-import:0617_22")
      (libsource (lib "eagle-import") (part "R-EU_0617/22"))
    )
    (comp (ref "S2")
      (value "R-EU_0617/22")
      (footprint "eagle-import:0617_22")
      (libsource (lib "eagle-import") (part "R-EU_0617/22"))
    )
    (comp (ref "S3")
      (value "R-EU_0617/22")
      (footprint "eagle-import:0617_22")
      (libsource (lib "eagle-import") (part "R-EU_0617/22"))
    )
    (comp (ref "S4")
      (value "R-EU_0617/22")
      (footprint "eagle-import:0617_22")
      (libsource (lib "eagle-import") (part "R-EU_0617/22"))
    )
    (comp (ref "S5")
      (value "R-EU_0617/22")
      (footprint "eagle-import:0617_22")
      (libsource (lib "eagle-import") (part "R-EU_0617/22"))
    )
    (comp (ref "S6")
      (value "R-EU_0617/22")
      (footprint "eagle-import:0617_22")
      (libsource (lib "eagle-import") (part "R-EU_0617/22"))
    )
    (comp (ref "S7")
      (value "R-EU_0617/22")
      (footprint "eagle-import:0617_22")
      (libsource (lib "eagle-import") (part "R-EU_0617/22"))
    )
    (comp (ref "S8")
      (value "R-EU_0617/22")
      (footprint "eagle-import:0617_22")
      (libsource (lib "eagle-import") (part "R-EU_0617/22"))
    )
    (comp (ref "S9")
      (value "R-EU_0617/22")
      (footprint "eagle-import:0617_22")
      (libsource (lib "eagle-import") (part "R-EU_0617/22"))
    )
    (comp (ref "S10")
      (value "R-EU_0617/22")
      (footprint "eagle-import:0617_22")
      (libsource (lib "eagle-import") (part "R-EU_0617/22"))
    )
    (comp (ref "S11")
      (value "R-EU_0617/22")
      (footprint "eagle-import:0617_22")
      (libsource (lib "eagle-import") (part "R-EU_0617/22"))
    )
    (comp (ref "S12")
      (value "R-EU_0617/22")
      (footprint "eagle-import:0617_22")
      (libsource (lib "eagle-import") (part "R-EU_0617/22"))
    )
    (comp (ref "S13")
      (value "R-EU_0617/22")
      (footprint "eagle-import:0617_22")
      (libsource (lib "eagle-import") (part "R-EU_0617/22"))
    )
    (comp (ref "S14")
      (value "R-EU_0617/22")
      (footprint "eagle-import:0617_22")
      (libsource (lib "eagle-import") (part "R-EU_0617/22"))
    )
    (comp (ref "S15")
      (value "R-EU_0617/22")
      (footprint "eagle-import:0617_22")
      (libsource (lib "eagle-import") (part "R-EU_0617/22"))
    )
    (comp (ref "S16")
      (value "R-EU_0617/22")
      (footprint "eagle-import:0617_22")
      (libsource (lib "eagle-import") (part "R-EU_0617/22"))
    )
    (comp (ref "S17")
      (value "R-EU_0617/22")
      (footprint "eagle-import:0617_22")
      (libsource (lib "eagle-import") (part "R-EU_0617/22"))
    )
    (comp (ref "S18")
      (value "R-EU_0617/22")
      (footprint "eagle-import:0617_22")
      (libsource (lib "eagle-import") (part "R-EU_0617/22"))
    )
    (comp (ref "S19")
      (value "R-EU_0617/22")
      (footprint "eagle-import:0617_22")
      (libsource (lib "eagle-import") (part "R-EU_0617/22"))
    )
    (comp (ref "S20")
      (value "R-EU_0617/22")
      (footprint "eagle-import:0617_22")
      (libsource (lib "eagle-import") (part "R-EU_0617/22"))
    )
    (comp (ref "S21")
      (value "R-EU_0617/22")
      (footprint "eagle-import:0617_22")
      (libsource (lib "eagle-import") (part "R-EU_0617/22"))
    )
    (comp (ref "S22")
      (value "R-EU_0617/22")
      (footprint "eagle-import:0617_22")
      (libsource (lib "eagle-import") (part "R-EU_0617/22"))
    )
    (comp (ref "S23")
      (value "R-EU_0617/22")
      (footprint "eagle-import:0617_22")
      (libsource (lib "eagle-import") (part "R-EU_0617/22"))
    )
    (comp (ref "S24")
      (value "R-EU_0617/22")
      (footprint "eagle-import:0617_22")
      (libsource (lib "eagle-import") (part "R-EU_0617/22"))
    )
    (comp (ref "S25")
      (value "R-EU_0617/22")
      (footprint "eagle-import:0617_22")
      (libsource (lib "eagle-import") (part "R-EU_0617/22"))
    )
    (comp (ref "S26")
      (value "R-EU_0617/22")
      (footprint "eagle-import:0617_22")
      (libsource (lib "eagle-import") (part "R-EU_0617/22"))
    )
    (comp (ref "S27")
      (value "R-EU_0617/22")
      (footprint "eagle-import:0617_22")
      (libsource (lib "eagle-import") (part "R-EU_0617/22"))
    )
    (comp (ref "S28")
      (value "R-EU_0617/22")
      (footprint "eagle-import:0617_22")
      (libsource (lib "eagle-import") (part "R-EU_0617/22"))
    )
    (comp (ref "S29")
      (value "R-EU_0617/22")
      (footprint "eagle-import:0617_22")
      (libsource (lib "eagle-import") (part "R-EU_0617/22"))
    )
    (comp (ref "S30")
      (value "R-EU_0617/22")
      (footprint "eagle-import:0617_22")
      (libsource (lib "eagle-import") (part "R-EU_0617/22"))
    )
    (comp (ref "S31")
      (value "R-EU_0617/22")
      (footprint "eagle-import:0617_22")
      (libsource (lib "eagle-import") (part "R-EU_0617/22"))
    )
    (comp (ref "S32")
      (value "R-EU_0617/22")
      (footprint "eagle-import:0617_22")
      (libsource (lib "eagle-import") (part "R-EU_0617/22"))
    )
    (comp (ref "S33")
      (value "R-EU_0617/22")
      (footprint "eagle-import:0617_22")
      (libsource (lib "eagle-import") (part "R-EU_0617/22"))
    )
    (comp (ref "S34")
      (value "R-EU_0617/22")
      (footprint "eagle-import:0617_22")
      (libsource (lib "eagle-import") (part "R-EU_0617/22"))
    )
    (comp (ref "S35")
      (value "R-EU_0617/22")
      (footprint "eagle-import:0617_22")
      (libsource (lib "eagle-import") (part "R-EU_0617/22"))
    )
    (comp (ref "S36")
      (value "R-EU_0617/22")
      (footprint "eagle-import:0617_22")
      (libsource (lib "eagle-import") (part "R-EU_0617/22"))
    )
    (comp (ref "S37")
      (value "R-EU_0617/22")
      (footprint "eagle-import:0617_22")
      (libsource (lib "eagle-import") (part "R-EU_0617/22"))
    )
    (comp (ref "S38")
      (value "R-EU_0617/22")
      (footprint "eagle-import:0617_22")
      (libsource (lib "eagle-import") (part "R-EU_0617/22"))
    )
    (comp (ref "S39")
      (value "R-EU_0617/22")
      (footprint "eagle-import:0617_22")
      (libsource (lib "eagle-import") (part "R-EU_0617/22"))
    )
    (comp (ref "S40")
      (value "R-EU_0617/22")
      (footprint "eagle-import:0617_22")
      (libsource (lib "eagle-import") (part "R-EU_0617/22"))
    )
    (comp (ref "S41")
      (value "R-EU_0617/22")
      (footprint "eagle-import:0617_22")
      (libsource (lib "eagle-import") (part "R-EU_0617/22"))
    )
    (comp (ref "S42")
      (value "R-EU_0617/22")
      (footprint "eagle-import:0617_22")
      (libsource (lib "eagle-import") (part "R-EU_0617/22"))
    )
    (comp (ref "S43")
      (value "R-EU_0617/22")
      (footprint "eagle-import:0617_22")
      (libsource (lib "eagle-import") (part "R-EU_0617/22"))
    )
    (comp (ref "S44")
      (value "R-EU_0617/22")
      (footprint "eagle-import:0617_22")
      (libsource (lib "eagle-import") (part "R-EU_0617/22"))
    )
    (comp (ref "S45")
      (value "R-EU_0617/22")
      (footprint "eagle-import:0617_22")
      (libsource (lib "eagle-import") (part "R-EU_0617/22"))
    )
    (comp (ref "S46")
      (value "R-EU_0617/22")
      (footprint "eagle-import:0617_22")
      (libsource (lib "eagle-import") (part "R-EU_0617/22"))
    )
    (comp (ref "S47")
      (value "R-EU_0617/22")
      (footprint "eagle-import:0617_22")
      (libsource (lib "eagle-import") (part "R-EU_0617/22"))
    )
    (comp (ref "S48")
      (value "R-EU_0617/22")
      (footprint "eagle-import:0617_22")
      (libsource (lib "eagle-import") (part "R-EU_0617/22"))
    )
    (comp (ref "S49")
      (value "R-EU_0617/22")
      (footprint "eagle-import:0617_22")
      (libsource (lib "eagle-import") (part "R-EU_0617/22"))
    )
    (comp (ref "S50")
      (value "R-EU_0617/22")
      (footprint "eagle-import:0617_22")
      (libsource (lib "eagle-import") (part "R-EU_0617/22"))
    )
    (comp (ref "S51")
      (value "R-EU_0617/22")
      (footprint "eagle-import:0617_22")
      (libsource (lib "eagle-import") (part "R-EU_0617/22"))
    )
    (comp (ref "S52")
      (value "R-EU_0617/22")
      (footprint "eagle-import:0617_22")
      (libsource (lib "eagle-import") (part "R-EU_0617/22"))
    )
    (comp (ref "S53")
      (value "R-EU_0617/22")
      (footprint "eagle-import:0617_22")
      (libsource (lib "eagle-import") (part "R-EU_0617/22"))
    )
    (comp (ref "S54")
      (value "R-EU_0617/22")
      (footprint "eagle-import:0617_22")
      (libsource (lib "eagle-import") (part "R-EU_0617/22"))
    )
    (comp (ref "S55")
      (value "R-EU_0617/22")
      (footprint "eagle-import:0617_22")
      (libsource (lib "eagle-import") (part "R-EU_0617/22"))
    )
    (comp (ref "S56")
      (value "R-EU_0617/22")
      (footprint "eagle-import:0617_22")
      (libsource (lib "eagle-import") (part "R-EU_0617/22"))
    )
    (comp (ref "S57")
      (value "R-EU_0617/22")
      (footprint "eagle-import:0617_22")
      (libsource (lib "eagle-import") (part "R-EU_0617/22"))
    )
    (comp (ref "S58")
      (value "R-EU_0617/22")
      (footprint "eagle-import:0617_22")
      (libsource (lib "eagle-import") (part "R-EU_0617/22"))
    )
    (comp (ref "S59")
      (value "R-EU_0617/22")
      (footprint "eagle-import:0617_22")
      (libsource (lib "eagle-import") (part "R-EU_0617/22"))
    )
    (comp (ref "S60")
      (value "R-EU_0617/22")
      (footprint "eagle-import:0617_22")
      (libsource (lib "eagle-import") (part "R-EU_0617/22"))
    )
    (comp (ref "S61")
      (value "R-EU_0617/22")
      (footprint "eagle-import:0617_22")
      (libsource (lib "eagle-import") (part "R-EU_0617/22"))
    )
    (comp (ref "S62")
      (value "R-EU_0617/22")
      (footprint "eagle-import:0617_22")
      (libsource (lib "eagle-import") (part "R-EU_0617/22"))
    )
    (comp (ref "S63")
      (value "R-EU_0617/22")
      (footprint "eagle-import:0617_22")
      (libsource (lib "eagle-import") (part "R-EU_0617/22"))
    )
    (comp (ref "S64")
      (value "R-EU_0617/22")
      (footprint "eagle-import:0617_22")
      (libsource (lib "eagle-import") (part "R-EU_0617/22"))
    )
  )
  (nets
    (net (code "4") (name "CLK") (class "Default")
      (node (ref "IC12") (pin "10") (pinfunction "CLK_10") (pintype "input"))
      (node (ref "IC13") (pin "10") (pinfunction "CLK_10") (pintype "input"))
      (node (ref "IC14") (pin "10") (pinfunction "CLK_10") (pintype "input"))
      (node (ref "IC15") (pin "10") (pinfunction "CLK_10") (pintype "input"))
      (node (ref "IC16") (pin "10") (pinfunction "CLK_10") (pintype "input"))
      (node (ref "IC17") (pin "10") (pinfunction "CLK_10") (pintype "input"))
      (node (ref "IC18") (pin "10") (pinfunction "CLK_10") (pintype "input"))
      (node (ref "IC19") (pin "10") (pinfunction "CLK_10") (pintype "input"))
      (node (ref "IC20") (pin "10") (pinfunction "CLK_10") (pintype "input"))
      (node (ref "IC21") (pin "10") (pinfunction "CLK_10") (pintype "input"))
      (node (ref "JP1") (pin "11") (pinfunction "11_11") (pintype "passive"))
    )
    (net (code "5") (name "G") (class "Default")
      (node (ref "IC1") (pin "13") (pinfunction "G_13") (pintype "input"))
      (node (ref "IC10") (pin "13") (pinfunction "G_13") (pintype "input"))
      (node (ref "IC11") (pin "13") (pinfunction "G_13") (pintype "input"))
      (node (ref "IC2") (pin "13") (pinfunction "G_13") (pintype "input"))
      (node (ref "IC3") (pin "13") (pinfunction "G_13") (pintype "input"))
      (node (ref "IC4") (pin "13") (pinfunction "G_13") (pintype "input"))
      (node (ref "IC5") (pin "13") (pinfunction "G_13") (pintype "input"))
      (node (ref "IC6") (pin "13") (pinfunction "G_13") (pintype "input"))
      (node (ref "IC7") (pin "13") (pinfunction "G_13") (pintype "input"))
      (node (ref "IC8") (pin "13") (pinfunction "G_13") (pintype "input"))
      (node (ref "IC9") (pin "13") (pinfunction "G_13") (pintype "input"))
      (node (ref "JP1") (pin "3") (pinfunction "3_3") (pintype "passive"))
    )
    (net (code "6") (name "GND") (class "Default")
      (node (ref "IC12") (pin "8") (pinfunction "VSS_8") (pintype "power_in"))
      (node (ref "IC13") (pin "8") (pinfunction "VSS_8") (pintype "power_in"))
      (node (ref "IC14") (pin "8") (pinfunction "VSS_8") (pintype "power_in"))
      (node (ref "IC15") (pin "8") (pinfunction "VSS_8") (pintype "power_in"))
      (node (ref "IC16") (pin "8") (pinfunction "VSS_8") (pintype "power_in"))
      (node (ref "IC17") (pin "8") (pinfunction "VSS_8") (pintype "power_in"))
      (node (ref "IC18") (pin "8") (pinfunction "VSS_8") (pintype "power_in"))
      (node (ref "IC19") (pin "8") (pinfunction "VSS_8") (pintype "power_in"))
      (node (ref "IC20") (pin "8") (pinfunction "VSS_8") (pintype "power_in"))
      (node (ref "IC21") (pin "8") (pinfunction "VSS_8") (pintype "power_in"))
      (node (ref "JP1") (pin "13") (pinfunction "13_13") (pintype "passive"))
      (node (ref "JP2") (pin "1") (pinfunction "1_1") (pintype "passive"))
      (node (ref "LED1") (pin "K") (pinfunction "C_K") (pintype "passive"))
      (node (ref "LED10") (pin "K") (pinfunction "C_K") (pintype "passive"))
      (node (ref "LED11") (pin "K") (pinfunction "C_K") (pintype "passive"))
      (node (ref "LED12") (pin "K") (pinfunction "C_K") (pintype "passive"))
      (node (ref "LED13") (pin "K") (pinfunction "C_K") (pintype "passive"))
      (node (ref "LED14") (pin "K") (pinfunction "C_K") (pintype "passive"))
      (node (ref "LED15") (pin "K") (pinfunction "C_K") (pintype "passive"))
      (node (ref "LED16") (pin "K") (pinfunction "C_K") (pintype "passive"))
      (node (ref "LED17") (pin "K") (pinfunction "C_K") (pintype "passive"))
      (node (ref "LED18") (pin "K") (pinfunction "C_K") (pintype "passive"))
      (node (ref "LED19") (pin "K") (pinfunction "C_K") (pintype "passive"))
      (node (ref "LED2") (pin "K") (pinfunction "C_K") (pintype "passive"))
      (node (ref "LED20") (pin "K") (pinfunction "C_K") (pintype "passive"))
      (node (ref "LED21") (pin "K") (pinfunction "C_K") (pintype "passive"))
      (node (ref "LED22") (pin "K") (pinfunction "C_K") (pintype "passive"))
      (node (ref "LED23") (pin "K") (pinfunction "C_K") (pintype "passive"))
      (node (ref "LED24") (pin "K") (pinfunction "C_K") (pintype "passive"))
      (node (ref "LED25") (pin "K") (pinfunction "C_K") (pintype "passive"))
      (node (ref "LED26") (pin "K") (pinfunction "C_K") (pintype "passive"))
      (node (ref "LED27") (pin "K") (pinfunction "C_K") (pintype "passive"))
      (node (ref "LED28") (pin "K") (pinfunction "C_K") (pintype "passive"))
      (node (ref "LED29") (pin "K") (pinfunction "C_K") (pintype "passive"))
      (node (ref "LED3") (pin "K") (pinfunction "C_K") (pintype "passive"))
      (node (ref "LED30") (pin "K") (pinfunction "C_K") (pintype "passive"))
      (node (ref "LED31") (pin "K") (pinfunction "C_K") (pintype "passive"))
      (node (ref "LED32") (pin "K") (pinfunction "C_K") (pintype "passive"))
      (node (ref "LED33") (pin "K") (pinfunction "C_K") (pintype "passive"))
      (node (ref "LED34") (pin "K") (pinfunction "C_K") (pintype "passive"))
      (node (ref "LED35") (pin "K") (pinfunction "C_K") (pintype "passive"))
      (node (ref "LED36") (pin "K") (pinfunction "C_K") (pintype "passive"))
      (node (ref "LED37") (pin "K") (pinfunction "C_K") (pintype "passive"))
      (node (ref "LED38") (pin "K") (pinfunction "C_K") (pintype "passive"))
      (node (ref "LED39") (pin "K") (pinfunction "C_K") (pintype "passive"))
      (node (ref "LED4") (pin "K") (pinfunction "C_K") (pintype "passive"))
      (node (ref "LED40") (pin "K") (pinfunction "C_K") (pintype "passive"))
      (node (ref "LED41") (pin "K") (pinfunction "C_K") (pintype "passive"))
      (node (ref "LED42") (pin "K") (pinfunction "C_K") (pintype "passive"))
      (node (ref "LED43") (pin "K") (pinfunction "C_K") (pintype "passive"))
      (node (ref "LED44") (pin "K") (pinfunction "C_K") (pintype "passive"))
      (node (ref "LED45") (pin "K") (pinfunction "C_K") (pintype "passive"))
      (node (ref "LED46") (pin "K") (pinfunction "C_K") (pintype "passive"))
      (node (ref "LED47") (pin "K") (pinfunction "C_K") (pintype "passive"))
      (node (ref "LED48") (pin "K") (pinfunction "C_K") (pintype "passive"))
      (node (ref "LED49") (pin "K") (pinfunction "C_K") (pintype "passive"))
      (node (ref "LED5") (pin "K") (pinfunction "C_K") (pintype "passive"))
      (node (ref "LED50") (pin "K") (pinfunction "C_K") (pintype "passive"))
      (node (ref "LED51") (pin "K") (pinfunction "C_K") (pintype "passive"))
      (node (ref "LED52") (pin "K") (pinfunction "C_K") (pintype "passive"))
      (node (ref "LED53") (pin "K") (pinfunction "C_K") (pintype "passive"))
      (node (ref "LED54") (pin "K") (pinfunction "C_K") (pintype "passive"))
      (node (ref "LED55") (pin "K") (pinfunction "C_K") (pintype "passive"))
      (node (ref "LED56") (pin "K") (pinfunction "C_K") (pintype "passive"))
      (node (ref "LED57") (pin "K") (pinfunction "C_K") (pintype "passive"))
      (node (ref "LED58") (pin "K") (pinfunction "C_K") (pintype "passive"))
      (node (ref "LED59") (pin "K") (pinfunction "C_K") (pintype "passive"))
      (node (ref "LED6") (pin "K") (pinfunction "C_K") (pintype "passive"))
      (node (ref "LED60") (pin "K") (pinfunction "C_K") (pintype "passive"))
      (node (ref "LED61") (pin "K") (pinfunction "C_K") (pintype "passive"))
      (node (ref "LED62") (pin "K") (pinfunction "C_K") (pintype "passive"))
      (node (ref "LED63") (pin "K") (pinfunction "C_K") (pintype "passive"))
      (node (ref "LED64") (pin "K") (pinfunction "C_K") (pintype "passive"))
      (node (ref "LED65") (pin "K") (pinfunction "C_K") (pintype "passive"))
      (node (ref "LED66") (pin "K") (pinfunction "C_K") (pintype "passive"))
      (node (ref "LED67") (pin "K") (pinfunction "C_K") (pintype "passive"))
      (node (ref "LED68") (pin "K") (pinfunction "C_K") (pintype "passive"))
      (node (ref "LED69") (pin "K") (pinfunction "C_K") (pintype "passive"))
      (node (ref "LED7") (pin "K") (pinfunction "C_K") (pintype "passive"))
      (node (ref "LED70") (pin "K") (pinfunction "C_K") (pintype "passive"))
      (node (ref "LED71") (pin "K") (pinfunction "C_K") (pintype "passive"))
      (node (ref "LED72") (pin "K") (pinfunction "C_K") (pintype "passive"))
      (node (ref "LED73") (pin "K") (pinfunction "C_K") (pintype "passive"))
      (node (ref "LED74") (pin "K") (pinfunction "C_K") (pintype "passive"))
      (node (ref "LED75") (pin "K") (pinfunction "C_K") (pintype "passive"))
      (node (ref "LED76") (pin "K") (pinfunction "C_K") (pintype "passive"))
      (node (ref "LED77") (pin "K") (pinfunction "C_K") (pintype "passive"))
      (node (ref "LED78") (pin "K") (pinfunction "C_K") (pintype "passive"))
      (node (ref "LED79") (pin "K") (pinfunction "C_K") (pintype "passive"))
      (node (ref "LED8") (pin "K") (pinfunction "C_K") (pintype "passive"))
      (node (ref "LED80") (pin "K") (pinfunction "C_K") (pintype "passive"))
      (node (ref "LED81") (pin "K") (pinfunction "C_K") (pintype "passive"))
      (node (ref "LED9") (pin "K") (pinfunction "C_K") (pintype "passive"))
      (node (ref "R1") (pin "1") (pinfunction "1_1") (pintype "passive"))
      (node (ref "R10") (pin "1") (pinfunction "1_1") (pintype "passive"))
      (node (ref "R11") (pin "1") (pinfunction "1_1") (pintype "passive"))
      (node (ref "R12") (pin "1") (pinfunction "1_1") (pintype "passive"))
      (node (ref "R13") (pin "1") (pinfunction "1_1") (pintype "passive"))
      (node (ref "R14") (pin "1") (pinfunction "1_1") (pintype "passive"))
      (node (ref "R15") (pin "1") (pinfunction "1_1") (pintype "passive"))
      (node (ref "R16") (pin "1") (pinfunction "1_1") (pintype "passive"))
      (node (ref "R17") (pin "1") (pinfunction "1_1") (pintype "passive"))
      (node (ref "R18") (pin "1") (pinfunction "1_1") (pintype "passive"))
      (node (ref "R19") (pin "1") (pinfunction "1_1") (pintype "passive"))
      (node (ref "R2") (pin "1") (pinfunction "1_1") (pintype "passive"))
      (node (ref "R20") (pin "1") (pinfunction "1_1") (pintype "passive"))
      (node (ref "R21") (pin "1") (pinfunction "1_1") (pintype "passive"))
      (node (ref "R22") (pin "1") (pinfunction "1_1") (pintype "passive"))
      (node (ref "R23") (pin "1") (pinfunction "1_1") (pintype "passive"))
      (node (ref "R24") (pin "1") (pinfunction "1_1") (pintype "passive"))
      (node (ref "R25") (pin "1") (pinfunction "1_1") (pintype "passive"))
      (node (ref "R26") (pin "1") (pinfunction "1_1") (pintype "passive"))
      (node (ref "R27") (pin "1") (pinfunction "1_1") (pintype "passive"))
      (node (ref "R28") (pin "1") (pinfunction "1_1") (pintype "passive"))
      (node (ref "R29") (pin "1") (pinfunction "1_1") (pintype "passive"))
      (node (ref "R3") (pin "1") (pinfunction "1_1") (pintype "passive"))
      (node (ref "R30") (pin "1") (pinfunction "1_1") (pintype "passive"))
      (node (ref "R31") (pin "1") (pinfunction "1_1") (pintype "passive"))
      (node (ref "R32") (pin "1") (pinfunction "1_1") (pintype "passive"))
      (node (ref "R33") (pin "1") (pinfunction "1_1") (pintype "passive"))
      (node (ref "R34") (pin "1") (pinfunction "1_1") (pintype "passive"))
      (node (ref "R35") (pin "1") (pinfunction "1_1") (pintype "passive"))
      (node (ref "R36") (pin "1") (pinfunction "1_1") (pintype "passive"))
      (node (ref "R37") (pin "1") (pinfunction "1_1") (pintype "passive"))
      (node (ref "R38") (pin "1") (pinfunction "1_1") (pintype "passive"))
      (node (ref "R39") (pin "1") (pinfunction "1_1") (pintype "passive"))
      (node (ref "R4") (pin "1") (pinfunction "1_1") (pintype "passive"))
      (node (ref "R40") (pin "1") (pinfunction "1_1") (pintype "passive"))
      (node (ref "R41") (pin "1") (pinfunction "1_1") (pintype "passive"))
      (node (ref "R42") (pin "1") (pinfunction "1_1") (pintype "passive"))
      (node (ref "R43") (pin "1") (pinfunction "1_1") (pintype "passive"))
      (node (ref "R44") (pin "1") (pinfunction "1_1") (pintype "passive"))
      (node (ref "R45") (pin "1") (pinfunction "1_1") (pintype "passive"))
      (node (ref "R46") (pin "1") (pinfunction "1_1") (pintype "passive"))
      (node (ref "R47") (pin "1") (pinfunction "1_1") (pintype "passive"))
      (node (ref "R48") (pin "1") (pinfunction "1_1") (pintype "passive"))
      (node (ref "R49") (pin "1") (pinfunction "1_1") (pintype "passive"))
      (node (ref "R5") (pin "1") (pinfunction "1_1") (pintype "passive"))
      (node (ref "R50") (pin "1") (pinfunction "1_1") (pintype "passive"))
      (node (ref "R51") (pin "1") (pinfunction "1_1") (pintype "passive"))
      (node (ref "R52") (pin "1") (pinfunction "1_1") (pintype "passive"))
      (node (ref "R53") (pin "1") (pinfunction "1_1") (pintype "passive"))
      (node (ref "R54") (pin "1") (pinfunction "1_1") (pintype "passive"))
      (node (ref "R55") (pin "1") (pinfunction "1_1") (pintype "passive"))
      (node (ref "R56") (pin "1") (pinfunction "1_1") (pintype "passive"))
      (node (ref "R57") (pin "1") (pinfunction "1_1") (pintype "passive"))
      (node (ref "R58") (pin "1") (pinfunction "1_1") (pintype "passive"))
      (node (ref "R59") (pin "1") (pinfunction "1_1") (pintype "passive"))
      (node (ref "R6") (pin "1") (pinfunction "1_1") (pintype "passive"))
      (node (ref "R60") (pin "1") (pinfunction "1_1") (pintype "passive"))
      (node (ref "R61") (pin "1") (pinfunction "1_1") (pintype "passive"))
      (node (ref "R62") (pin "1") (pinfunction "1_1") (pintype "passive"))
      (node (ref "R63") (pin "1") (pinfunction "1_1") (pintype "passive"))
      (node (ref "R64") (pin "1") (pinfunction "1_1") (pintype "passive"))
      (node (ref "R65") (pin "1") (pinfunction "1_1") (pintype "passive"))
      (node (ref "R66") (pin "1") (pinfunction "1_1") (pintype "passive"))
      (node (ref "R67") (pin "1") (pinfunction "1_1") (pintype "passive"))
      (node (ref "R68") (pin "1") (pinfunction "1_1") (pintype "passive"))
      (node (ref "R69") (pin "1") (pinfunction "1_1") (pintype "passive"))
      (node (ref "R7") (pin "1") (pinfunction "1_1") (pintype "passive"))
      (node (ref "R70") (pin "1") (pinfunction "1_1") (pintype "passive"))
      (node (ref "R71") (pin "1") (pinfunction "1_1") (pintype "passive"))
      (node (ref "R72") (pin "1") (pinfunction "1_1") (pintype "passive"))
      (node (ref "R73") (pin "1") (pinfunction "1_1") (pintype "passive"))
      (node (ref "R74") (pin "1") (pinfunction "1_1") (pintype "passive"))
      (node (ref "R75") (pin "1") (pinfunction "1_1") (pintype "passive"))
      (node (ref "R76") (pin "1") (pinfunction "1_1") (pintype "passive"))
      (node (ref "R77") (pin "1") (pinfunction "1_1") (pintype "passive"))
      (node (ref "R78") (pin "1") (pinfunction "1_1") (pintype "passive"))
      (node (ref "R79") (pin "1") (pinfunction "1_1") (pintype "passive"))
      (node (ref "R8") (pin "1") (pinfunction "1_1") (pintype "passive"))
      (node (ref "R80") (pin "1") (pinfunction "1_1") (pintype "passive"))
      (node (ref "R9") (pin "1") (pinfunction "1_1") (pintype "passive"))
    )
    (net (code "7") (name "Net-(IC1A-QA)") (class "Default")
      (node (ref "IC1") (pin "15") (pinfunction "QA_15") (pintype "tri_state"))
      (node (ref "LED1") (pin "A") (pinfunction "A_A") (pintype "passive"))
    )
    (net (code "8") (name "Net-(IC1A-QB)") (class "Default")
      (node (ref "IC1") (pin "1") (pinfunction "QB_1") (pintype "tri_state"))
      (node (ref "LED5") (pin "A") (pinfunction "A_A") (pintype "passive"))
    )
    (net (code "9") (name "Net-(IC1A-QC)") (class "Default")
      (node (ref "IC1") (pin "2") (pinfunction "QC_2") (pintype "tri_state"))
      (node (ref "LED6") (pin "A") (pinfunction "A_A") (pintype "passive"))
    )
    (net (code "10") (name "Net-(IC1A-QD)") (class "Default")
      (node (ref "IC1") (pin "3") (pinfunction "QD_3") (pintype "tri_state"))
      (node (ref "LED2") (pin "A") (pinfunction "A_A") (pintype "passive"))
    )
    (net (code "11") (name "Net-(IC1A-QE)") (class "Default")
      (node (ref "IC1") (pin "4") (pinfunction "QE_4") (pintype "tri_state"))
      (node (ref "LED7") (pin "A") (pinfunction "A_A") (pintype "passive"))
    )
    (net (code "12") (name "Net-(IC1A-QF)") (class "Default")
      (node (ref "IC1") (pin "5") (pinfunction "QF_5") (pintype "tri_state"))
      (node (ref "LED8") (pin "A") (pinfunction "A_A") (pintype "passive"))
    )
    (net (code "13") (name "Net-(IC1A-QG)") (class "Default")
      (node (ref "IC1") (pin "6") (pinfunction "QG_6") (pintype "tri_state"))
      (node (ref "LED4") (pin "A") (pinfunction "A_A") (pintype "passive"))
    )
    (net (code "14") (name "Net-(IC1A-QH)") (class "Default")
      (node (ref "IC1") (pin "7") (pinfunction "QH_7") (pintype "tri_state"))
      (node (ref "LED3") (pin "A") (pinfunction "A_A") (pintype "passive"))
    )
    (net (code "15") (name "Net-(IC1A-QH*)") (class "Default")
      (node (ref "IC1") (pin "9") (pinfunction "QH*_9") (pintype "tri_state"))
      (node (ref "IC2") (pin "14") (pinfunction "SER_14") (pintype "input"))
    )
    (net (code "16") (name "Net-(IC2A-QA)") (class "Default")
      (node (ref "IC2") (pin "15") (pinfunction "QA_15") (pintype "tri_state"))
      (node (ref "LED9") (pin "A") (pinfunction "A_A") (pintype "passive"))
    )
    (net (code "17") (name "Net-(IC2A-QC)") (class "Default")
      (node (ref "IC2") (pin "2") (pinfunction "QC_2") (pintype "tri_state"))
      (node (ref "LED14") (pin "A") (pinfunction "A_A") (pintype "passive"))
    )
    (net (code "18") (name "Net-(IC2A-QD)") (class "Default")
      (node (ref "IC2") (pin "3") (pinfunction "QD_3") (pintype "tri_state"))
      (node (ref "LED10") (pin "A") (pinfunction "A_A") (pintype "passive"))
    )
    (net (code "19") (name "Net-(IC2A-QE)") (class "Default")
      (node (ref "IC2") (pin "4") (pinfunction "QE_4") (pintype "tri_state"))
      (node (ref "LED15") (pin "A") (pinfunction "A_A") (pintype "passive"))
    )
    (net (code "20") (name "Net-(IC2A-QF)") (class "Default")
      (node (ref "IC2") (pin "5") (pinfunction "QF_5") (pintype "tri_state"))
      (node (ref "LED16") (pin "A") (pinfunction "A_A") (pintype "passive"))
    )
    (net (code "21") (name "Net-(IC2A-QG)") (class "Default")
      (node (ref "IC2") (pin "6") (pinfunction "QG_6") (pintype "tri_state"))
      (node (ref "LED12") (pin "A") (pinfunction "A_A") (pintype "passive"))
    )
    (net (code "22") (name "Net-(IC2A-QH)") (class "Default")
      (node (ref "IC2") (pin "7") (pinfunction "QH_7") (pintype "tri_state"))
      (node (ref "LED11") (pin "A") (pinfunction "A_A") (pintype "passive"))
    )
    (net (code "23") (name "Net-(IC2A-QH*)") (class "Default")
      (node (ref "IC2") (pin "9") (pinfunction "QH*_9") (pintype "tri_state"))
      (node (ref "IC3") (pin "14") (pinfunction "SER_14") (pintype "input"))
    )
    (net (code "24") (name "Net-(IC3A-QA)") (class "Default")
      (node (ref "IC3") (pin "15") (pinfunction "QA_15") (pintype "tri_state"))
      (node (ref "LED17") (pin "A") (pinfunction "A_A") (pintype "passive"))
    )
    (net (code "25") (name "Net-(IC3A-QC)") (class "Default")
      (node (ref "IC3") (pin "2") (pinfunction "QC_2") (pintype "tri_state"))
      (node (ref "LED22") (pin "A") (pinfunction "A_A") (pintype "passive"))
    )
    (net (code "26") (name "Net-(IC3A-QD)") (class "Default")
      (node (ref "IC3") (pin "3") (pinfunction "QD_3") (pintype "tri_state"))
      (node (ref "LED18") (pin "A") (pinfunction "A_A") (pintype "passive"))
    )
    (net (code "27") (name "Net-(IC3A-QE)") (class "Default")
      (node (ref "IC3") (pin "4") (pinfunction "QE_4") (pintype "tri_state"))
      (node (ref "LED23") (pin "A") (pinfunction "A_A") (pintype "passive"))
    )
    (net (code "28") (name "Net-(IC3A-QF)") (class "Default")
      (node (ref "IC3") (pin "5") (pinfunction "QF_5") (pintype "tri_state"))
      (node (ref "LED24") (pin "A") (pinfunction "A_A") (pintype "passive"))
    )
    (net (code "29") (name "Net-(IC3A-QG)") (class "Default")
      (node (ref "IC3") (pin "6") (pinfunction "QG_6") (pintype "tri_state"))
      (node (ref "LED20") (pin "A") (pinfunction "A_A") (pintype "passive"))
    )
    (net (code "30") (name "Net-(IC3A-QH)") (class "Default")
      (node (ref "IC3") (pin "7") (pinfunction "QH_7") (pintype "tri_state"))
      (node (ref "LED19") (pin "A") (pinfunction "A_A") (pintype "passive"))
    )
    (net (code "31") (name "Net-(IC3A-QH*)") (class "Default")
      (node (ref "IC3") (pin "9") (pinfunction "QH*_9") (pintype "tri_state"))
      (node (ref "IC4") (pin "14") (pinfunction "SER_14") (pintype "input"))
    )
    (net (code "32") (name "Net-(IC4A-QA)") (class "Default")
      (node (ref "IC4") (pin "15") (pinfunction "QA_15") (pintype "tri_state"))
      (node (ref "LED25") (pin "A") (pinfunction "A_A") (pintype "passive"))
    )
    (net (code "33") (name "Net-(IC4A-QC)") (class "Default")
      (node (ref "IC4") (pin "2") (pinfunction "QC_2") (pintype "tri_state"))
      (node (ref "LED30") (pin "A") (pinfunction "A_A") (pintype "passive"))
    )
    (net (code "34") (name "Net-(IC4A-QD)") (class "Default")
      (node (ref "IC4") (pin "3") (pinfunction "QD_3") (pintype "tri_state"))
      (node (ref "LED26") (pin "A") (pinfunction "A_A") (pintype "passive"))
    )
    (net (code "35") (name "Net-(IC4A-QE)") (class "Default")
      (node (ref "IC4") (pin "4") (pinfunction "QE_4") (pintype "tri_state"))
      (node (ref "LED31") (pin "A") (pinfunction "A_A") (pintype "passive"))
    )
    (net (code "36") (name "Net-(IC4A-QF)") (class "Default")
      (node (ref "IC4") (pin "5") (pinfunction "QF_5") (pintype "tri_state"))
      (node (ref "LED32") (pin "A") (pinfunction "A_A") (pintype "passive"))
    )
    (net (code "37") (name "Net-(IC4A-QG)") (class "Default")
      (node (ref "IC4") (pin "6") (pinfunction "QG_6") (pintype "tri_state"))
      (node (ref "LED28") (pin "A") (pinfunction "A_A") (pintype "passive"))
    )
    (net (code "38") (name "Net-(IC4A-QH)") (class "Default")
      (node (ref "IC4") (pin "7") (pinfunction "QH_7") (pintype "tri_state"))
      (node (ref "LED27") (pin "A") (pinfunction "A_A") (pintype "passive"))
    )
    (net (code "39") (name "Net-(IC4A-QH*)") (class "Default")
      (node (ref "IC4") (pin "9") (pinfunction "QH*_9") (pintype "tri_state"))
      (node (ref "IC5") (pin "14") (pinfunction "SER_14") (pintype "input"))
    )
    (net (code "40") (name "Net-(IC5A-QA)") (class "Default")
      (node (ref "IC5") (pin "15") (pinfunction "QA_15") (pintype "tri_state"))
      (node (ref "LED33") (pin "A") (pinfunction "A_A") (pintype "passive"))
    )
    (net (code "41") (name "Net-(IC5A-QC)") (class "Default")
      (node (ref "IC5") (pin "2") (pinfunction "QC_2") (pintype "tri_state"))
      (node (ref "LED38") (pin "A") (pinfunction "A_A") (pintype "passive"))
    )
    (net (code "42") (name "Net-(IC5A-QD)") (class "Default")
      (node (ref "IC5") (pin "3") (pinfunction "QD_3") (pintype "tri_state"))
      (node (ref "LED34") (pin "A") (pinfunction "A_A") (pintype "passive"))
    )
    (net (code "43") (name "Net-(IC5A-QE)") (class "Default")
      (node (ref "IC5") (pin "4") (pinfunction "QE_4") (pintype "tri_state"))
      (node (ref "LED39") (pin "A") (pinfunction "A_A") (pintype "passive"))
    )
    (net (code "44") (name "Net-(IC5A-QF)") (class "Default")
      (node (ref "IC5") (pin "5") (pinfunction "QF_5") (pintype "tri_state"))
      (node (ref "LED40") (pin "A") (pinfunction "A_A") (pintype "passive"))
    )
    (net (code "45") (name "Net-(IC5A-QG)") (class "Default")
      (node (ref "IC5") (pin "6") (pinfunction "QG_6") (pintype "tri_state"))
      (node (ref "LED36") (pin "A") (pinfunction "A_A") (pintype "passive"))
    )
    (net (code "46") (name "Net-(IC5A-QH)") (class "Default")
      (node (ref "IC5") (pin "7") (pinfunction "QH_7") (pintype "tri_state"))
      (node (ref "LED35") (pin "A") (pinfunction "A_A") (pintype "passive"))
    )
    (net (code "47") (name "Net-(IC5A-QH*)") (class "Default")
      (node (ref "IC5") (pin "9") (pinfunction "QH*_9") (pintype "tri_state"))
      (node (ref "IC6") (pin "14") (pinfunction "SER_14") (pintype "input"))
    )
    (net (code "48") (name "Net-(IC6A-QA)") (class "Default")
      (node (ref "IC6") (pin "15") (pinfunction "QA_15") (pintype "tri_state"))
      (node (ref "LED41") (pin "A") (pinfunction "A_A") (pintype "passive"))
    )
    (net (code "49") (name "Net-(IC6A-QC)") (class "Default")
      (node (ref "IC6") (pin "2") (pinfunction "QC_2") (pintype "tri_state"))
      (node (ref "LED46") (pin "A") (pinfunction "A_A") (pintype "passive"))
    )
    (net (code "50") (name "Net-(IC6A-QD)") (class "Default")
      (node (ref "IC6") (pin "3") (pinfunction "QD_3") (pintype "tri_state"))
      (node (ref "LED42") (pin "A") (pinfunction "A_A") (pintype "passive"))
    )
    (net (code "51") (name "Net-(IC6A-QE)") (class "Default")
      (node (ref "IC6") (pin "4") (pinfunction "QE_4") (pintype "tri_state"))
      (node (ref "LED47") (pin "A") (pinfunction "A_A") (pintype "passive"))
    )
    (net (code "52") (name "Net-(IC6A-QF)") (class "Default")
      (node (ref "IC6") (pin "5") (pinfunction "QF_5") (pintype "tri_state"))
      (node (ref "LED48") (pin "A") (pinfunction "A_A") (pintype "passive"))
    )
    (net (code "53") (name "Net-(IC6A-QG)") (class "Default")
      (node (ref "IC6") (pin "6") (pinfunction "QG_6") (pintype "tri_state"))
      (node (ref "LED44") (pin "A") (pinfunction "A_A") (pintype "passive"))
    )
    (net (code "54") (name "Net-(IC6A-QH)") (class "Default")
      (node (ref "IC6") (pin "7") (pinfunction "QH_7") (pintype "tri_state"))
      (node (ref "LED43") (pin "A") (pinfunction "A_A") (pintype "passive"))
    )
    (net (code "55") (name "Net-(IC6A-QH*)") (class "Default")
      (node (ref "IC6") (pin "9") (pinfunction "QH*_9") (pintype "tri_state"))
      (node (ref "IC7") (pin "14") (pinfunction "SER_14") (pintype "input"))
    )
    (net (code "56") (name "Net-(IC7A-QA)") (class "Default")
      (node (ref "IC7") (pin "15") (pinfunction "QA_15") (pintype "tri_state"))
      (node (ref "LED49") (pin "A") (pinfunction "A_A") (pintype "passive"))
    )
    (net (code "57") (name "Net-(IC7A-QC)") (class "Default")
      (node (ref "IC7") (pin "2") (pinfunction "QC_2") (pintype "tri_state"))
      (node (ref "LED54") (pin "A") (pinfunction "A_A") (pintype "passive"))
    )
    (net (code "58") (name "Net-(IC7A-QD)") (class "Default")
      (node (ref "IC7") (pin "3") (pinfunction "QD_3") (pintype "tri_state"))
      (node (ref "LED50") (pin "A") (pinfunction "A_A") (pintype "passive"))
    )
    (net (code "59") (name "Net-(IC7A-QE)") (class "Default")
      (node (ref "IC7") (pin "4") (pinfunction "QE_4") (pintype "tri_state"))
      (node (ref "LED55") (pin "A") (pinfunction "A_A") (pintype "passive"))
    )
    (net (code "60") (name "Net-(IC7A-QF)") (class "Default")
      (node (ref "IC7") (pin "5") (pinfunction "QF_5") (pintype "tri_state"))
      (node (ref "LED56") (pin "A") (pinfunction "A_A") (pintype "passive"))
    )
    (net (code "61") (name "Net-(IC7A-QG)") (class "Default")
      (node (ref "IC7") (pin "6") (pinfunction "QG_6") (pintype "tri_state"))
      (node (ref "LED52") (pin "A") (pinfunction "A_A") (pintype "passive"))
    )
    (net (code "62") (name "Net-(IC7A-QH)") (class "Default")
      (node (ref "IC7") (pin "7") (pinfunction "QH_7") (pintype "tri_state"))
      (node (ref "LED51") (pin "A") (pinfunction "A_A") (pintype "passive"))
    )
    (net (code "63") (name "Net-(IC7A-QH*)") (class "Default")
      (node (ref "IC7") (pin "9") (pinfunction "QH*_9") (pintype "tri_state"))
      (node (ref "IC8") (pin "14") (pinfunction "SER_14") (pintype "input"))
    )
    (net (code "64") (name "Net-(IC8A-QA)") (class "Default")
      (node (ref "IC8") (pin "15") (pinfunction "QA_15") (pintype "tri_state"))
      (node (ref "LED57") (pin "A") (pinfunction "A_A") (pintype "passive"))
    )
    (net (code "65") (name "Net-(IC8A-QC)") (class "Default")
      (node (ref "IC8") (pin "2") (pinfunction "QC_2") (pintype "tri_state"))
      (node (ref "LED62") (pin "A") (pinfunction "A_A") (pintype "passive"))
    )
    (net (code "66") (name "Net-(IC8A-QD)") (class "Default")
      (node (ref "IC8") (pin "3") (pinfunction "QD_3") (pintype "tri_state"))
      (node (ref "LED58") (pin "A") (pinfunction "A_A") (pintype "passive"))
    )
    (net (code "67") (name "Net-(IC8A-QE)") (class "Default")
      (node (ref "IC8") (pin "4") (pinfunction "QE_4") (pintype "tri_state"))
      (node (ref "LED63") (pin "A") (pinfunction "A_A") (pintype "passive"))
    )
    (net (code "68") (name "Net-(IC8A-QF)") (class "Default")
      (node (ref "IC8") (pin "5") (pinfunction "QF_5") (pintype "tri_state"))
      (node (ref "LED64") (pin "A") (pinfunction "A_A") (pintype "passive"))
    )
    (net (code "69") (name "Net-(IC8A-QG)") (class "Default")
      (node (ref "IC8") (pin "6") (pinfunction "QG_6") (pintype "tri_state"))
      (node (ref "LED60") (pin "A") (pinfunction "A_A") (pintype "passive"))
    )
    (net (code "70") (name "Net-(IC8A-QH)") (class "Default")
      (node (ref "IC8") (pin "7") (pinfunction "QH_7") (pintype "tri_state"))
      (node (ref "LED59") (pin "A") (pinfunction "A_A") (pintype "passive"))
    )
    (net (code "71") (name "Net-(IC8A-QH*)") (class "Default")
      (node (ref "IC8") (pin "9") (pinfunction "QH*_9") (pintype "tri_state"))
      (node (ref "IC9") (pin "14") (pinfunction "SER_14") (pintype "input"))
    )
    (net (code "72") (name "Net-(IC9A-QA)") (class "Default")
      (node (ref "IC9") (pin "15") (pinfunction "QA_15") (pintype "tri_state"))
      (node (ref "LED65") (pin "A") (pinfunction "A_A") (pintype "passive"))
    )
    (net (code "73") (name "Net-(IC9A-QC)") (class "Default")
      (node (ref "IC9") (pin "2") (pinfunction "QC_2") (pintype "tri_state"))
      (node (ref "LED70") (pin "A") (pinfunction "A_A") (pintype "passive"))
    )
    (net (code "74") (name "Net-(IC9A-QD)") (class "Default")
      (node (ref "IC9") (pin "3") (pinfunction "QD_3") (pintype "tri_state"))
      (node (ref "LED66") (pin "A") (pinfunction "A_A") (pintype "passive"))
    )
    (net (code "75") (name "Net-(IC9A-QE)") (class "Default")
      (node (ref "IC9") (pin "4") (pinfunction "QE_4") (pintype "tri_state"))
      (node (ref "LED71") (pin "A") (pinfunction "A_A") (pintype "passive"))
    )
    (net (code "76") (name "Net-(IC9A-QF)") (class "Default")
      (node (ref "IC9") (pin "5") (pinfunction "QF_5") (pintype "tri_state"))
      (node (ref "LED72") (pin "A") (pinfunction "A_A") (pintype "passive"))
    )
    (net (code "77") (name "Net-(IC9A-QG)") (class "Default")
      (node (ref "IC9") (pin "6") (pinfunction "QG_6") (pintype "tri_state"))
      (node (ref "LED68") (pin "A") (pinfunction "A_A") (pintype "passive"))
    )
    (net (code "78") (name "Net-(IC9A-QH)") (class "Default")
      (node (ref "IC9") (pin "7") (pinfunction "QH_7") (pintype "tri_state"))
      (node (ref "LED67") (pin "A") (pinfunction "A_A") (pintype "passive"))
    )
    (net (code "79") (name "Net-(IC10A-QA)") (class "Default")
      (node (ref "IC10") (pin "15") (pinfunction "QA_15") (pintype "tri_state"))
      (node (ref "LED73") (pin "A") (pinfunction "A_A") (pintype "passive"))
    )
    (net (code "80") (name "Net-(IC10A-QC)") (class "Default")
      (node (ref "IC10") (pin "2") (pinfunction "QC_2") (pintype "tri_state"))
      (node (ref "LED78") (pin "A") (pinfunction "A_A") (pintype "passive"))
    )
    (net (code "81") (name "Net-(IC10A-QD)") (class "Default")
      (node (ref "IC10") (pin "3") (pinfunction "QD_3") (pintype "tri_state"))
      (node (ref "LED74") (pin "A") (pinfunction "A_A") (pintype "passive"))
    )
    (net (code "82") (name "Net-(IC10A-QE)") (class "Default")
      (node (ref "IC10") (pin "4") (pinfunction "QE_4") (pintype "tri_state"))
      (node (ref "LED79") (pin "A") (pinfunction "A_A") (pintype "passive"))
    )
    (net (code "83") (name "Net-(IC10A-QF)") (class "Default")
      (node (ref "IC10") (pin "5") (pinfunction "QF_5") (pintype "tri_state"))
      (node (ref "LED80") (pin "A") (pinfunction "A_A") (pintype "passive"))
    )
    (net (code "84") (name "Net-(IC10A-QG)") (class "Default")
      (node (ref "IC10") (pin "6") (pinfunction "QG_6") (pintype "tri_state"))
      (node (ref "LED76") (pin "A") (pinfunction "A_A") (pintype "passive"))
    )
    (net (code "85") (name "Net-(IC10A-QH)") (class "Default")
      (node (ref "IC10") (pin "7") (pinfunction "QH_7") (pintype "tri_state"))
      (node (ref "LED75") (pin "A") (pinfunction "A_A") (pintype "passive"))
    )
    (net (code "86") (name "Net-(IC10A-QH*)") (class "Default")
      (node (ref "IC10") (pin "9") (pinfunction "QH*_9") (pintype "tri_state"))
      (node (ref "IC11") (pin "14") (pinfunction "SER_14") (pintype "input"))
    )
    (net (code "87") (name "Net-(IC10A-SER)") (class "Default")
      (node (ref "IC10") (pin "14") (pinfunction "SER_14") (pintype "input"))
      (node (ref "IC9") (pin "9") (pinfunction "QH*_9") (pintype "tri_state"))
    )
    (net (code "88") (name "Net-(IC11A-QA)") (class "Default")
      (node (ref "IC11") (pin "15") (pinfunction "QA_15") (pintype "tri_state"))
      (node (ref "LED81") (pin "A") (pinfunction "A_A") (pintype "passive"))
    )
    (net (code "89") (name "Net-(IC12A-P1)") (class "Default")
      (node (ref "IC12") (pin "7") (pinfunction "P1_7") (pintype "input"))
      (node (ref "R4") (pin "2") (pinfunction "2_2") (pintype "passive"))
      (node (ref "S4") (pin "1") (pinfunction "1_1") (pintype "passive"))
    )
    (net (code "90") (name "Net-(IC12A-P2)") (class "Default")
      (node (ref "IC12") (pin "6") (pinfunction "P2_6") (pintype "input"))
      (node (ref "R8") (pin "2") (pinfunction "2_2") (pintype "passive"))
      (node (ref "S8") (pin "1") (pinfunction "1_1") (pintype "passive"))
    )
    (net (code "91") (name "Net-(IC12A-P3)") (class "Default")
      (node (ref "IC12") (pin "5") (pinfunction "P3_5") (pintype "input"))
      (node (ref "R7") (pin "2") (pinfunction "2_2") (pintype "passive"))
      (node (ref "S7") (pin "1") (pinfunction "1_1") (pintype "passive"))
    )
    (net (code "92") (name "Net-(IC12A-P4)") (class "Default")
      (node (ref "IC12") (pin "4") (pinfunction "P4_4") (pintype "input"))
      (node (ref "R6") (pin "2") (pinfunction "2_2") (pintype "passive"))
      (node (ref "S6") (pin "1") (pinfunction "1_1") (pintype "passive"))
    )
    (net (code "93") (name "Net-(IC12A-P5)") (class "Default")
      (node (ref "IC12") (pin "13") (pinfunction "P5_13") (pintype "input"))
      (node (ref "R3") (pin "2") (pinfunction "2_2") (pintype "passive"))
      (node (ref "S3") (pin "1") (pinfunction "1_1") (pintype "passive"))
    )
    (net (code "94") (name "Net-(IC12A-P6)") (class "Default")
      (node (ref "IC12") (pin "14") (pinfunction "P6_14") (pintype "input"))
      (node (ref "R2") (pin "2") (pinfunction "2_2") (pintype "passive"))
      (node (ref "S2") (pin "1") (pinfunction "1_1") (pintype "passive"))
    )
    (net (code "95") (name "Net-(IC12A-P7)") (class "Default")
      (node (ref "IC12") (pin "15") (pinfunction "P7_15") (pintype "input"))
      (node (ref "R1") (pin "2") (pinfunction "2_2") (pintype "passive"))
      (node (ref "S1") (pin "1") (pinfunction "1_1") (pintype "passive"))
    )
    (net (code "96") (name "Net-(IC12A-P8)") (class "Default")
      (node (ref "IC12") (pin "1") (pinfunction "P8_1") (pintype "input"))
      (node (ref "R5") (pin "2") (pinfunction "2_2") (pintype "passive"))
      (node (ref "S5") (pin "1") (pinfunction "1_1") (pintype "passive"))
    )
    (net (code "97") (name "Net-(IC12A-Q8)") (class "Default")
      (node (ref "IC12") (pin "3") (pinfunction "Q8_3") (pintype "output"))
      (node (ref "JP1") (pin "10") (pinfunction "10_10") (pintype "passive"))
    )
    (net (code "98") (name "Net-(IC12A-SI)") (class "Default")
      (node (ref "IC12") (pin "11") (pinfunction "SI_11") (pintype "input"))
      (node (ref "IC13") (pin "3") (pinfunction "Q8_3") (pintype "output"))
    )
    (net (code "99") (name "Net-(IC13A-P1)") (class "Default")
      (node (ref "IC13") (pin "7") (pinfunction "P1_7") (pintype "input"))
      (node (ref "R12") (pin "2") (pinfunction "2_2") (pintype "passive"))
      (node (ref "S12") (pin "1") (pinfunction "1_1") (pintype "passive"))
    )
    (net (code "100") (name "Net-(IC13A-P2)") (class "Default")
      (node (ref "IC13") (pin "6") (pinfunction "P2_6") (pintype "input"))
      (node (ref "R16") (pin "2") (pinfunction "2_2") (pintype "passive"))
      (node (ref "S16") (pin "1") (pinfunction "1_1") (pintype "passive"))
    )
    (net (code "101") (name "Net-(IC13A-P3)") (class "Default")
      (node (ref "IC13") (pin "5") (pinfunction "P3_5") (pintype "input"))
      (node (ref "R15") (pin "2") (pinfunction "2_2") (pintype "passive"))
      (node (ref "S15") (pin "1") (pinfunction "1_1") (pintype "passive"))
    )
    (net (code "102") (name "Net-(IC13A-P4)") (class "Default")
      (node (ref "IC13") (pin "4") (pinfunction "P4_4") (pintype "input"))
      (node (ref "R14") (pin "2") (pinfunction "2_2") (pintype "passive"))
      (node (ref "S14") (pin "1") (pinfunction "1_1") (pintype "passive"))
    )
    (net (code "103") (name "Net-(IC13A-P5)") (class "Default")
      (node (ref "IC13") (pin "13") (pinfunction "P5_13") (pintype "input"))
      (node (ref "R11") (pin "2") (pinfunction "2_2") (pintype "passive"))
      (node (ref "S11") (pin "1") (pinfunction "1_1") (pintype "passive"))
    )
    (net (code "104") (name "Net-(IC13A-P6)") (class "Default")
      (node (ref "IC13") (pin "14") (pinfunction "P6_14") (pintype "input"))
      (node (ref "R10") (pin "2") (pinfunction "2_2") (pintype "passive"))
      (node (ref "S10") (pin "1") (pinfunction "1_1") (pintype "passive"))
    )
    (net (code "105") (name "Net-(IC13A-P7)") (class "Default")
      (node (ref "IC13") (pin "15") (pinfunction "P7_15") (pintype "input"))
      (node (ref "R9") (pin "2") (pinfunction "2_2") (pintype "passive"))
      (node (ref "S9") (pin "1") (pinfunction "1_1") (pintype "passive"))
    )
    (net (code "106") (name "Net-(IC13A-P8)") (class "Default")
      (node (ref "IC13") (pin "1") (pinfunction "P8_1") (pintype "input"))
      (node (ref "R13") (pin "2") (pinfunction "2_2") (pintype "passive"))
      (node (ref "S13") (pin "1") (pinfunction "1_1") (pintype "passive"))
    )
    (net (code "107") (name "Net-(IC13A-SI)") (class "Default")
      (node (ref "IC13") (pin "11") (pinfunction "SI_11") (pintype "input"))
      (node (ref "IC14") (pin "3") (pinfunction "Q8_3") (pintype "output"))
    )
    (net (code "108") (name "Net-(IC14A-P1)") (class "Default")
      (node (ref "IC14") (pin "7") (pinfunction "P1_7") (pintype "input"))
      (node (ref "R20") (pin "2") (pinfunction "2_2") (pintype "passive"))
      (node (ref "S20") (pin "1") (pinfunction "1_1") (pintype "passive"))
    )
    (net (code "109") (name "Net-(IC14A-P2)") (class "Default")
      (node (ref "IC14") (pin "6") (pinfunction "P2_6") (pintype "input"))
      (node (ref "R24") (pin "2") (pinfunction "2_2") (pintype "passive"))
      (node (ref "S24") (pin "1") (pinfunction "1_1") (pintype "passive"))
    )
    (net (code "110") (name "Net-(IC14A-P3)") (class "Default")
      (node (ref "IC14") (pin "5") (pinfunction "P3_5") (pintype "input"))
      (node (ref "R23") (pin "2") (pinfunction "2_2") (pintype "passive"))
      (node (ref "S23") (pin "1") (pinfunction "1_1") (pintype "passive"))
    )
    (net (code "111") (name "Net-(IC14A-P4)") (class "Default")
      (node (ref "IC14") (pin "4") (pinfunction "P4_4") (pintype "input"))
      (node (ref "R22") (pin "2") (pinfunction "2_2") (pintype "passive"))
      (node (ref "S22") (pin "1") (pinfunction "1_1") (pintype "passive"))
    )
    (net (code "112") (name "Net-(IC14A-P5)") (class "Default")
      (node (ref "IC14") (pin "13") (pinfunction "P5_13") (pintype "input"))
      (node (ref "R19") (pin "2") (pinfunction "2_2") (pintype "passive"))
      (node (ref "S19") (pin "1") (pinfunction "1_1") (pintype "passive"))
    )
    (net (code "113") (name "Net-(IC14A-P6)") (class "Default")
      (node (ref "IC14") (pin "14") (pinfunction "P6_14") (pintype "input"))
      (node (ref "R18") (pin "2") (pinfunction "2_2") (pintype "passive"))
      (node (ref "S18") (pin "1") (pinfunction "1_1") (pintype "passive"))
    )
    (net (code "114") (name "Net-(IC14A-P7)") (class "Default")
      (node (ref "IC14") (pin "15") (pinfunction "P7_15") (pintype "input"))
      (node (ref "R17") (pin "2") (pinfunction "2_2") (pintype "passive"))
      (node (ref "S17") (pin "1") (pinfunction "1_1") (pintype "passive"))
    )
    (net (code "115") (name "Net-(IC14A-P8)") (class "Default")
      (node (ref "IC14") (pin "1") (pinfunction "P8_1") (pintype "input"))
      (node (ref "R21") (pin "2") (pinfunction "2_2") (pintype "passive"))
      (node (ref "S21") (pin "1") (pinfunction "1_1") (pintype "passive"))
    )
    (net (code "116") (name "Net-(IC14A-SI)") (class "Default")
      (node (ref "IC14") (pin "11") (pinfunction "SI_11") (pintype "input"))
      (node (ref "IC15") (pin "3") (pinfunction "Q8_3") (pintype "output"))
    )
    (net (code "117") (name "Net-(IC15A-P1)") (class "Default")
      (node (ref "IC15") (pin "7") (pinfunction "P1_7") (pintype "input"))
      (node (ref "R28") (pin "2") (pinfunction "2_2") (pintype "passive"))
      (node (ref "S28") (pin "1") (pinfunction "1_1") (pintype "passive"))
    )
    (net (code "118") (name "Net-(IC15A-P2)") (class "Default")
      (node (ref "IC15") (pin "6") (pinfunction "P2_6") (pintype "input"))
      (node (ref "R32") (pin "2") (pinfunction "2_2") (pintype "passive"))
      (node (ref "S32") (pin "1") (pinfunction "1_1") (pintype "passive"))
    )
    (net (code "119") (name "Net-(IC15A-P3)") (class "Default")
      (node (ref "IC15") (pin "5") (pinfunction "P3_5") (pintype "input"))
      (node (ref "R31") (pin "2") (pinfunction "2_2") (pintype "passive"))
      (node (ref "S31") (pin "1") (pinfunction "1_1") (pintype "passive"))
    )
    (net (code "120") (name "Net-(IC15A-P4)") (class "Default")
      (node (ref "IC15") (pin "4") (pinfunction "P4_4") (pintype "input"))
      (node (ref "R30") (pin "2") (pinfunction "2_2") (pintype "passive"))
      (node (ref "S30") (pin "1") (pinfunction "1_1") (pintype "passive"))
    )
    (net (code "121") (name "Net-(IC15A-P5)") (class "Default")
      (node (ref "IC15") (pin "13") (pinfunction "P5_13") (pintype "input"))
      (node (ref "R27") (pin "2") (pinfunction "2_2") (pintype "passive"))
      (node (ref "S27") (pin "1") (pinfunction "1_1") (pintype "passive"))
    )
    (net (code "122") (name "Net-(IC15A-P6)") (class "Default")
      (node (ref "IC15") (pin "14") (pinfunction "P6_14") (pintype "input"))
      (node (ref "R26") (pin "2") (pinfunction "2_2") (pintype "passive"))
      (node (ref "S26") (pin "1") (pinfunction "1_1") (pintype "passive"))
    )
    (net (code "123") (name "Net-(IC15A-P7)") (class "Default")
      (node (ref "IC15") (pin "15") (pinfunction "P7_15") (pintype "input"))
      (node (ref "R25") (pin "2") (pinfunction "2_2") (pintype "passive"))
      (node (ref "S25") (pin "1") (pinfunction "1_1") (pintype "passive"))
    )
    (net (code "124") (name "Net-(IC15A-P8)") (class "Default")
      (node (ref "IC15") (pin "1") (pinfunction "P8_1") (pintype "input"))
      (node (ref "R29") (pin "2") (pinfunction "2_2") (pintype "passive"))
      (node (ref "S29") (pin "1") (pinfunction "1_1") (pintype "passive"))
    )
    (net (code "125") (name "Net-(IC15A-SI)") (class "Default")
      (node (ref "IC15") (pin "11") (pinfunction "SI_11") (pintype "input"))
      (node (ref "IC16") (pin "3") (pinfunction "Q8_3") (pintype "output"))
    )
    (net (code "126") (name "Net-(IC16A-P1)") (class "Default")
      (node (ref "IC16") (pin "7") (pinfunction "P1_7") (pintype "input"))
      (node (ref "R36") (pin "2") (pinfunction "2_2") (pintype "passive"))
      (node (ref "S36") (pin "1") (pinfunction "1_1") (pintype "passive"))
    )
    (net (code "127") (name "Net-(IC16A-P2)") (class "Default")
      (node (ref "IC16") (pin "6") (pinfunction "P2_6") (pintype "input"))
      (node (ref "R40") (pin "2") (pinfunction "2_2") (pintype "passive"))
      (node (ref "S40") (pin "1") (pinfunction "1_1") (pintype "passive"))
    )
    (net (code "128") (name "Net-(IC16A-P3)") (class "Default")
      (node (ref "IC16") (pin "5") (pinfunction "P3_5") (pintype "input"))
      (node (ref "R39") (pin "2") (pinfunction "2_2") (pintype "passive"))
      (node (ref "S39") (pin "1") (pinfunction "1_1") (pintype "passive"))
    )
    (net (code "129") (name "Net-(IC16A-P4)") (class "Default")
      (node (ref "IC16") (pin "4") (pinfunction "P4_4") (pintype "input"))
      (node (ref "R38") (pin "2") (pinfunction "2_2") (pintype "passive"))
      (node (ref "S38") (pin "1") (pinfunction "1_1") (pintype "passive"))
    )
    (net (code "130") (name "Net-(IC16A-P5)") (class "Default")
      (node (ref "IC16") (pin "13") (pinfunction "P5_13") (pintype "input"))
      (node (ref "R35") (pin "2") (pinfunction "2_2") (pintype "passive"))
      (node (ref "S35") (pin "1") (pinfunction "1_1") (pintype "passive"))
    )
    (net (code "131") (name "Net-(IC16A-P6)") (class "Default")
      (node (ref "IC16") (pin "14") (pinfunction "P6_14") (pintype "input"))
      (node (ref "R34") (pin "2") (pinfunction "2_2") (pintype "passive"))
      (node (ref "S34") (pin "1") (pinfunction "1_1") (pintype "passive"))
    )
    (net (code "132") (name "Net-(IC16A-P7)") (class "Default")
      (node (ref "IC16") (pin "15") (pinfunction "P7_15") (pintype "input"))
      (node (ref "R33") (pin "2") (pinfunction "2_2") (pintype "passive"))
      (node (ref "S33") (pin "1") (pinfunction "1_1") (pintype "passive"))
    )
    (net (code "133") (name "Net-(IC16A-P8)") (class "Default")
      (node (ref "IC16") (pin "1") (pinfunction "P8_1") (pintype "input"))
      (node (ref "R37") (pin "2") (pinfunction "2_2") (pintype "passive"))
      (node (ref "S37") (pin "1") (pinfunction "1_1") (pintype "passive"))
    )
    (net (code "134") (name "Net-(IC16A-SI)") (class "Default")
      (node (ref "IC16") (pin "11") (pinfunction "SI_11") (pintype "input"))
      (node (ref "IC17") (pin "3") (pinfunction "Q8_3") (pintype "output"))
    )
    (net (code "135") (name "Net-(IC17A-P1)") (class "Default")
      (node (ref "IC17") (pin "7") (pinfunction "P1_7") (pintype "input"))
      (node (ref "R44") (pin "2") (pinfunction "2_2") (pintype "passive"))
      (node (ref "S44") (pin "1") (pinfunction "1_1") (pintype "passive"))
    )
    (net (code "136") (name "Net-(IC17A-P2)") (class "Default")
      (node (ref "IC17") (pin "6") (pinfunction "P2_6") (pintype "input"))
      (node (ref "R48") (pin "2") (pinfunction "2_2") (pintype "passive"))
      (node (ref "S48") (pin "1") (pinfunction "1_1") (pintype "passive"))
    )
    (net (code "137") (name "Net-(IC17A-P3)") (class "Default")
      (node (ref "IC17") (pin "5") (pinfunction "P3_5") (pintype "input"))
      (node (ref "R47") (pin "2") (pinfunction "2_2") (pintype "passive"))
      (node (ref "S47") (pin "1") (pinfunction "1_1") (pintype "passive"))
    )
    (net (code "138") (name "Net-(IC17A-P4)") (class "Default")
      (node (ref "IC17") (pin "4") (pinfunction "P4_4") (pintype "input"))
      (node (ref "R46") (pin "2") (pinfunction "2_2") (pintype "passive"))
      (node (ref "S46") (pin "1") (pinfunction "1_1") (pintype "passive"))
    )
    (net (code "139") (name "Net-(IC17A-P5)") (class "Default")
      (node (ref "IC17") (pin "13") (pinfunction "P5_13") (pintype "input"))
      (node (ref "R43") (pin "2") (pinfunction "2_2") (pintype "passive"))
      (node (ref "S43") (pin "1") (pinfunction "1_1") (pintype "passive"))
    )
    (net (code "140") (name "Net-(IC17A-P6)") (class "Default")
      (node (ref "IC17") (pin "14") (pinfunction "P6_14") (pintype "input"))
      (node (ref "R42") (pin "2") (pinfunction "2_2") (pintype "passive"))
      (node (ref "S42") (pin "1") (pinfunction "1_1") (pintype "passive"))
    )
    (net (code "141") (name "Net-(IC17A-P7)") (class "Default")
      (node (ref "IC17") (pin "15") (pinfunction "P7_15") (pintype "input"))
      (node (ref "R41") (pin "2") (pinfunction "2_2") (pintype "passive"))
      (node (ref "S41") (pin "1") (pinfunction "1_1") (pintype "passive"))
    )
    (net (code "142") (name "Net-(IC17A-P8)") (class "Default")
      (node (ref "IC17") (pin "1") (pinfunction "P8_1") (pintype "input"))
      (node (ref "R45") (pin "2") (pinfunction "2_2") (pintype "passive"))
      (node (ref "S45") (pin "1") (pinfunction "1_1") (pintype "passive"))
    )
    (net (code "143") (name "Net-(IC17A-SI)") (class "Default")
      (node (ref "IC17") (pin "11") (pinfunction "SI_11") (pintype "input"))
      (node (ref "IC18") (pin "3") (pinfunction "Q8_3") (pintype "output"))
    )
    (net (code "144") (name "Net-(IC18A-P1)") (class "Default")
      (node (ref "IC18") (pin "7") (pinfunction "P1_7") (pintype "input"))
      (node (ref "R52") (pin "2") (pinfunction "2_2") (pintype "passive"))
      (node (ref "S52") (pin "1") (pinfunction "1_1") (pintype "passive"))
    )
    (net (code "145") (name "Net-(IC18A-P2)") (class "Default")
      (node (ref "IC18") (pin "6") (pinfunction "P2_6") (pintype "input"))
      (node (ref "R56") (pin "2") (pinfunction "2_2") (pintype "passive"))
      (node (ref "S56") (pin "1") (pinfunction "1_1") (pintype "passive"))
    )
    (net (code "146") (name "Net-(IC18A-P3)") (class "Default")
      (node (ref "IC18") (pin "5") (pinfunction "P3_5") (pintype "input"))
      (node (ref "R55") (pin "2") (pinfunction "2_2") (pintype "passive"))
      (node (ref "S55") (pin "1") (pinfunction "1_1") (pintype "passive"))
    )
    (net (code "147") (name "Net-(IC18A-P4)") (class "Default")
      (node (ref "IC18") (pin "4") (pinfunction "P4_4") (pintype "input"))
      (node (ref "R54") (pin "2") (pinfunction "2_2") (pintype "passive"))
      (node (ref "S54") (pin "1") (pinfunction "1_1") (pintype "passive"))
    )
    (net (code "148") (name "Net-(IC18A-P5)") (class "Default")
      (node (ref "IC18") (pin "13") (pinfunction "P5_13") (pintype "input"))
      (node (ref "R51") (pin "2") (pinfunction "2_2") (pintype "passive"))
      (node (ref "S51") (pin "1") (pinfunction "1_1") (pintype "passive"))
    )
    (net (code "149") (name "Net-(IC18A-P6)") (class "Default")
      (node (ref "IC18") (pin "14") (pinfunction "P6_14") (pintype "input"))
      (node (ref "R50") (pin "2") (pinfunction "2_2") (pintype "passive"))
      (node (ref "S50") (pin "1") (pinfunction "1_1") (pintype "passive"))
    )
    (net (code "150") (name "Net-(IC18A-P7)") (class "Default")
      (node (ref "IC18") (pin "15") (pinfunction "P7_15") (pintype "input"))
      (node (ref "R49") (pin "2") (pinfunction "2_2") (pintype "passive"))
      (node (ref "S49") (pin "1") (pinfunction "1_1") (pintype "passive"))
    )
    (net (code "151") (name "Net-(IC18A-P8)") (class "Default")
      (node (ref "IC18") (pin "1") (pinfunction "P8_1") (pintype "input"))
      (node (ref "R53") (pin "2") (pinfunction "2_2") (pintype "passive"))
      (node (ref "S53") (pin "1") (pinfunction "1_1") (pintype "passive"))
    )
    (net (code "152") (name "Net-(IC18A-SI)") (class "Default")
      (node (ref "IC18") (pin "11") (pinfunction "SI_11") (pintype "input"))
      (node (ref "IC19") (pin "3") (pinfunction "Q8_3") (pintype "output"))
    )
    (net (code "153") (name "Net-(IC19A-P1)") (class "Default")
      (node (ref "IC19") (pin "7") (pinfunction "P1_7") (pintype "input"))
      (node (ref "R60") (pin "2") (pinfunction "2_2") (pintype "passive"))
      (node (ref "S60") (pin "1") (pinfunction "1_1") (pintype "passive"))
    )
    (net (code "154") (name "Net-(IC19A-P2)") (class "Default")
      (node (ref "IC19") (pin "6") (pinfunction "P2_6") (pintype "input"))
      (node (ref "R64") (pin "2") (pinfunction "2_2") (pintype "passive"))
      (node (ref "S64") (pin "1") (pinfunction "1_1") (pintype "passive"))
    )
    (net (code "155") (name "Net-(IC19A-P3)") (class "Default")
      (node (ref "IC19") (pin "5") (pinfunction "P3_5") (pintype "input"))
      (node (ref "R63") (pin "2") (pinfunction "2_2") (pintype "passive"))
      (node (ref "S63") (pin "1") (pinfunction "1_1") (pintype "passive"))
    )
    (net (code "156") (name "Net-(IC19A-P4)") (class "Default")
      (node (ref "IC19") (pin "4") (pinfunction "P4_4") (pintype "input"))
      (node (ref "R62") (pin "2") (pinfunction "2_2") (pintype "passive"))
      (node (ref "S62") (pin "1") (pinfunction "1_1") (pintype "passive"))
    )
    (net (code "157") (name "Net-(IC19A-P5)") (class "Default")
      (node (ref "IC19") (pin "13") (pinfunction "P5_13") (pintype "input"))
      (node (ref "R59") (pin "2") (pinfunction "2_2") (pintype "passive"))
      (node (ref "S59") (pin "1") (pinfunction "1_1") (pintype "passive"))
    )
    (net (code "158") (name "Net-(IC19A-P6)") (class "Default")
      (node (ref "IC19") (pin "14") (pinfunction "P6_14") (pintype "input"))
      (node (ref "R58") (pin "2") (pinfunction "2_2") (pintype "passive"))
      (node (ref "S58") (pin "1") (pinfunction "1_1") (pintype "passive"))
    )
    (net (code "159") (name "Net-(IC19A-P7)") (class "Default")
      (node (ref "IC19") (pin "15") (pinfunction "P7_15") (pintype "input"))
      (node (ref "R57") (pin "2") (pinfunction "2_2") (pintype "passive"))
      (node (ref "S57") (pin "1") (pinfunction "1_1") (pintype "passive"))
    )
    (net (code "160") (name "Net-(IC19A-P8)") (class "Default")
      (node (ref "IC19") (pin "1") (pinfunction "P8_1") (pintype "input"))
      (node (ref "R61") (pin "2") (pinfunction "2_2") (pintype "passive"))
      (node (ref "S61") (pin "1") (pinfunction "1_1") (pintype "passive"))
    )
    (net (code "161") (name "Net-(IC19A-SI)") (class "Default")
      (node (ref "IC19") (pin "11") (pinfunction "SI_11") (pintype "input"))
      (node (ref "IC20") (pin "3") (pinfunction "Q8_3") (pintype "output"))
    )
    (net (code "162") (name "Net-(IC20A-SI)") (class "Default")
      (node (ref "IC20") (pin "11") (pinfunction "SI_11") (pintype "input"))
      (node (ref "IC21") (pin "3") (pinfunction "Q8_3") (pintype "output"))
    )
    (net (code "163") (name "PS") (class "Default")
      (node (ref "IC12") (pin "9") (pinfunction "P/~{S}_9") (pintype "input"))
      (node (ref "IC13") (pin "9") (pinfunction "P/~{S}_9") (pintype "input"))
      (node (ref "IC14") (pin "9") (pinfunction "P/~{S}_9") (pintype "input"))
      (node (ref "IC15") (pin "9") (pinfunction "P/~{S}_9") (pintype "input"))
      (node (ref "IC16") (pin "9") (pinfunction "P/~{S}_9") (pintype "input"))
      (node (ref "IC17") (pin "9") (pinfunction "P/~{S}_9") (pintype "input"))
      (node (ref "IC18") (pin "9") (pinfunction "P/~{S}_9") (pintype "input"))
      (node (ref "IC19") (pin "9") (pinfunction "P/~{S}_9") (pintype "input"))
      (node (ref "IC20") (pin "9") (pinfunction "P/~{S}_9") (pintype "input"))
      (node (ref "IC21") (pin "9") (pinfunction "P/~{S}_9") (pintype "input"))
      (node (ref "JP1") (pin "12") (pinfunction "12_12") (pintype "passive"))
    )
    (net (code "164") (name "RCK") (class "Default")
      (node (ref "IC1") (pin "12") (pinfunction "RCK_12") (pintype "input"))
      (node (ref "IC10") (pin "12") (pinfunction "RCK_12") (pintype "input"))
      (node (ref "IC11") (pin "12") (pinfunction "RCK_12") (pintype "input"))
      (node (ref "IC2") (pin "12") (pinfunction "RCK_12") (pintype "input"))
      (node (ref "IC3") (pin "12") (pinfunction "RCK_12") (pintype "input"))
      (node (ref "IC4") (pin "12") (pinfunction "RCK_12") (pintype "input"))
      (node (ref "IC5") (pin "12") (pinfunction "RCK_12") (pintype "input"))
      (node (ref "IC6") (pin "12") (pinfunction "RCK_12") (pintype "input"))
      (node (ref "IC7") (pin "12") (pinfunction "RCK_12") (pintype "input"))
      (node (ref "IC8") (pin "12") (pinfunction "RCK_12") (pintype "input"))
      (node (ref "IC9") (pin "12") (pinfunction "RCK_12") (pintype "input"))
      (node (ref "JP1") (pin "4") (pinfunction "4_4") (pintype "passive"))
    )
    (net (code "165") (name "SCK") (class "Default")
      (node (ref "IC1") (pin "11") (pinfunction "SCK_11") (pintype "input"))
      (node (ref "IC10") (pin "11") (pinfunction "SCK_11") (pintype "input"))
      (node (ref "IC11") (pin "11") (pinfunction "SCK_11") (pintype "input"))
      (node (ref "IC2") (pin "11") (pinfunction "SCK_11") (pintype "input"))
      (node (ref "IC3") (pin "11") (pinfunction "SCK_11") (pintype "input"))
      (node (ref "IC4") (pin "11") (pinfunction "SCK_11") (pintype "input"))
      (node (ref "IC5") (pin "11") (pinfunction "SCK_11") (pintype "input"))
      (node (ref "IC6") (pin "11") (pinfunction "SCK_11") (pintype "input"))
      (node (ref "IC7") (pin "11") (pinfunction "SCK_11") (pintype "input"))
      (node (ref "IC8") (pin "11") (pinfunction "SCK_11") (pintype "input"))
      (node (ref "IC9") (pin "11") (pinfunction "SCK_11") (pintype "input"))
      (node (ref "JP1") (pin "6") (pinfunction "6_6") (pintype "passive"))
    )
    (net (code "166") (name "SCL") (class "Default")
      (node (ref "IC1") (pin "10") (pinfunction "SCL_10") (pintype "input"))
      (node (ref "IC10") (pin "10") (pinfunction "SCL_10") (pintype "input"))
      (node (ref "IC11") (pin "10") (pinfunction "SCL_10") (pintype "input"))
      (node (ref "IC2") (pin "10") (pinfunction "SCL_10") (pintype "input"))
      (node (ref "IC3") (pin "10") (pinfunction "SCL_10") (pintype "input"))
      (node (ref "IC4") (pin "10") (pinfunction "SCL_10") (pintype "input"))
      (node (ref "IC5") (pin "10") (pinfunction "SCL_10") (pintype "input"))
      (node (ref "IC6") (pin "10") (pinfunction "SCL_10") (pintype "input"))
      (node (ref "IC7") (pin "10") (pinfunction "SCL_10") (pintype "input"))
      (node (ref "IC8") (pin "10") (pinfunction "SCL_10") (pintype "input"))
      (node (ref "IC9") (pin "10") (pinfunction "SCL_10") (pintype "input"))
      (node (ref "JP1") (pin "7") (pinfunction "7_7") (pintype "passive"))
    )
    (net (code "167") (name "SER") (class "Default")
      (node (ref "IC1") (pin "14") (pinfunction "SER_14") (pintype "input"))
      (node (ref "JP1") (pin "2") (pinfunction "2_2") (pintype "passive"))
    )
    (net (code "168") (name "SIDELED1") (class "Default")
      (node (ref "IC11") (pin "1") (pinfunction "QB_1") (pintype "tri_state"))
      (node (ref "JP2") (pin "18") (pinfunction "18_18") (pintype "passive"))
    )
    (net (code "169") (name "SIDELED2") (class "Default")
      (node (ref "IC11") (pin "2") (pinfunction "QC_2") (pintype "tri_state"))
      (node (ref "JP2") (pin "19") (pinfunction "19_19") (pintype "passive"))
    )
    (net (code "170") (name "SIDELED3") (class "Default")
      (node (ref "IC11") (pin "3") (pinfunction "QD_3") (pintype "tri_state"))
      (node (ref "JP2") (pin "20") (pinfunction "20_20") (pintype "passive"))
    )
    (net (code "171") (name "SIDELED4") (class "Default")
      (node (ref "IC11") (pin "4") (pinfunction "QE_4") (pintype "tri_state"))
      (node (ref "JP2") (pin "21") (pinfunction "21_21") (pintype "passive"))
    )
    (net (code "172") (name "SIDELED5") (class "Default")
      (node (ref "IC11") (pin "5") (pinfunction "QF_5") (pintype "tri_state"))
      (node (ref "JP2") (pin "22") (pinfunction "22_22") (pintype "passive"))
    )
    (net (code "173") (name "SIDELED6") (class "Default")
      (node (ref "IC11") (pin "6") (pinfunction "QG_6") (pintype "tri_state"))
      (node (ref "JP2") (pin "23") (pinfunction "23_23") (pintype "passive"))
    )
    (net (code "174") (name "SIDELED7") (class "Default")
      (node (ref "IC11") (pin "7") (pinfunction "QH_7") (pintype "tri_state"))
      (node (ref "JP2") (pin "24") (pinfunction "24_24") (pintype "passive"))
    )
    (net (code "175") (name "SIDESWITCH1") (class "Default")
      (node (ref "IC20") (pin "15") (pinfunction "P7_15") (pintype "input"))
      (node (ref "JP2") (pin "2") (pinfunction "2_2") (pintype "passive"))
      (node (ref "R65") (pin "2") (pinfunction "2_2") (pintype "passive"))
    )
    (net (code "176") (name "SIDESWITCH2") (class "Default")
      (node (ref "IC20") (pin "14") (pinfunction "P6_14") (pintype "input"))
      (node (ref "JP2") (pin "3") (pinfunction "3_3") (pintype "passive"))
      (node (ref "R66") (pin "2") (pinfunction "2_2") (pintype "passive"))
    )
    (net (code "177") (name "SIDESWITCH3") (class "Default")
      (node (ref "IC20") (pin "13") (pinfunction "P5_13") (pintype "input"))
      (node (ref "JP2") (pin "4") (pinfunction "4_4") (pintype "passive"))
      (node (ref "R67") (pin "2") (pinfunction "2_2") (pintype "passive"))
    )
    (net (code "178") (name "SIDESWITCH4") (class "Default")
      (node (ref "IC20") (pin "7") (pinfunction "P1_7") (pintype "input"))
      (node (ref "JP2") (pin "5") (pinfunction "5_5") (pintype "passive"))
      (node (ref "R68") (pin "2") (pinfunction "2_2") (pintype "passive"))
    )
    (net (code "179") (name "SIDESWITCH5") (class "Default")
      (node (ref "IC20") (pin "1") (pinfunction "P8_1") (pintype "input"))
      (node (ref "JP2") (pin "6") (pinfunction "6_6") (pintype "passive"))
      (node (ref "R69") (pin "2") (pinfunction "2_2") (pintype "passive"))
    )
    (net (code "180") (name "SIDESWITCH6") (class "Default")
      (node (ref "IC20") (pin "4") (pinfunction "P4_4") (pintype "input"))
      (node (ref "JP2") (pin "7") (pinfunction "7_7") (pintype "passive"))
      (node (ref "R70") (pin "2") (pinfunction "2_2") (pintype "passive"))
    )
    (net (code "181") (name "SIDESWITCH7") (class "Default")
      (node (ref "IC20") (pin "5") (pinfunction "P3_5") (pintype "input"))
      (node (ref "JP2") (pin "8") (pinfunction "8_8") (pintype "passive"))
      (node (ref "R71") (pin "2") (pinfunction "2_2") (pintype "passive"))
    )
    (net (code "182") (name "SIDESWITCH8") (class "Default")
      (node (ref "IC20") (pin "6") (pinfunction "P2_6") (pintype "input"))
      (node (ref "JP2") (pin "9") (pinfunction "9_9") (pintype "passive"))
      (node (ref "R72") (pin "2") (pinfunction "2_2") (pintype "passive"))
    )
    (net (code "183") (name "SIDESWITCH9") (class "Default")
      (node (ref "IC21") (pin "15") (pinfunction "P7_15") (pintype "input"))
      (node (ref "JP2") (pin "10") (pinfunction "10_10") (pintype "passive"))
      (node (ref "R73") (pin "2") (pinfunction "2_2") (pintype "passive"))
    )
    (net (code "184") (name "SIDESWITCH10") (class "Default")
      (node (ref "IC21") (pin "14") (pinfunction "P6_14") (pintype "input"))
      (node (ref "JP2") (pin "11") (pinfunction "11_11") (pintype "passive"))
      (node (ref "R74") (pin "2") (pinfunction "2_2") (pintype "passive"))
    )
    (net (code "185") (name "SIDESWITCH11") (class "Default")
      (node (ref "IC21") (pin "13") (pinfunction "P5_13") (pintype "input"))
      (node (ref "JP2") (pin "12") (pinfunction "12_12") (pintype "passive"))
      (node (ref "R75") (pin "2") (pinfunction "2_2") (pintype "passive"))
    )
    (net (code "186") (name "SIDESWITCH12") (class "Default")
      (node (ref "IC21") (pin "7") (pinfunction "P1_7") (pintype "input"))
      (node (ref "JP2") (pin "13") (pinfunction "13_13") (pintype "passive"))
      (node (ref "R76") (pin "2") (pinfunction "2_2") (pintype "passive"))
    )
    (net (code "187") (name "SIDESWITCH13") (class "Default")
      (node (ref "IC21") (pin "1") (pinfunction "P8_1") (pintype "input"))
      (node (ref "JP2") (pin "14") (pinfunction "14_14") (pintype "passive"))
      (node (ref "R77") (pin "2") (pinfunction "2_2") (pintype "passive"))
    )
    (net (code "188") (name "SIDESWITCH14") (class "Default")
      (node (ref "IC21") (pin "4") (pinfunction "P4_4") (pintype "input"))
      (node (ref "JP2") (pin "15") (pinfunction "15_15") (pintype "passive"))
      (node (ref "R78") (pin "2") (pinfunction "2_2") (pintype "passive"))
    )
    (net (code "189") (name "SIDESWITCH15") (class "Default")
      (node (ref "IC21") (pin "5") (pinfunction "P3_5") (pintype "input"))
      (node (ref "JP2") (pin "16") (pinfunction "16_16") (pintype "passive"))
      (node (ref "R79") (pin "2") (pinfunction "2_2") (pintype "passive"))
    )
    (net (code "190") (name "SIDESWITCH16") (class "Default")
      (node (ref "IC21") (pin "6") (pinfunction "P2_6") (pintype "input"))
      (node (ref "JP2") (pin "17") (pinfunction "17_17") (pintype "passive"))
      (node (ref "R80") (pin "2") (pinfunction "2_2") (pintype "passive"))
    )
    (net (code "191") (name "VCC") (class "Default")
      (node (ref "IC12") (pin "16") (pinfunction "VDD_16") (pintype "power_in"))
      (node (ref "IC13") (pin "16") (pinfunction "VDD_16") (pintype "power_in"))
      (node (ref "IC14") (pin "16") (pinfunction "VDD_16") (pintype "power_in"))
      (node (ref "IC15") (pin "16") (pinfunction "VDD_16") (pintype "power_in"))
      (node (ref "IC16") (pin "16") (pinfunction "VDD_16") (pintype "power_in"))
      (node (ref "IC17") (pin "16") (pinfunction "VDD_16") (pintype "power_in"))
      (node (ref "IC18") (pin "16") (pinfunction "VDD_16") (pintype "power_in"))
      (node (ref "IC19") (pin "16") (pinfunction "VDD_16") (pintype "power_in"))
      (node (ref "IC20") (pin "16") (pinfunction "VDD_16") (pintype "power_in"))
      (node (ref "IC21") (pin "16") (pinfunction "VDD_16") (pintype "power_in"))
      (node (ref "JP1") (pin "1") (pinfunction "1_1") (pintype "passive"))
      (node (ref "JP2") (pin "25") (pinfunction "25_25") (pintype "passive"))
      (node (ref "S1") (pin "2") (pinfunction "2_2") (pintype "passive"))
      (node (ref "S10") (pin "2") (pinfunction "2_2") (pintype "passive"))
      (node (ref "S11") (pin "2") (pinfunction "2_2") (pintype "passive"))
      (node (ref "S12") (pin "2") (pinfunction "2_2") (pintype "passive"))
      (node (ref "S13") (pin "2") (pinfunction "2_2") (pintype "passive"))
      (node (ref "S14") (pin "2") (pinfunction "2_2") (pintype "passive"))
      (node (ref "S15") (pin "2") (pinfunction "2_2") (pintype "passive"))
      (node (ref "S16") (pin "2") (pinfunction "2_2") (pintype "passive"))
      (node (ref "S17") (pin "2") (pinfunction "2_2") (pintype "passive"))
      (node (ref "S18") (pin "2") (pinfunction "2_2") (pintype "passive"))
      (node (ref "S19") (pin "2") (pinfunction "2_2") (pintype "passive"))
      (node (ref "S2") (pin "2") (pinfunction "2_2") (pintype "passive"))
      (node (ref "S20") (pin "2") (pinfunction "2_2") (pintype "passive"))
      (node (ref "S21") (pin "2") (pinfunction "2_2") (pintype "passive"))
      (node (ref "S22") (pin "2") (pinfunction "2_2") (pintype "passive"))
      (node (ref "S23") (pin "2") (pinfunction "2_2") (pintype "passive"))
      (node (ref "S24") (pin "2") (pinfunction "2_2") (pintype "passive"))
      (node (ref "S25") (pin "2") (pinfunction "2_2") (pintype "passive"))
      (node (ref "S26") (pin "2") (pinfunction "2_2") (pintype "passive"))
      (node (ref "S27") (pin "2") (pinfunction "2_2") (pintype "passive"))
      (node (ref "S28") (pin "2") (pinfunction "2_2") (pintype "passive"))
      (node (ref "S29") (pin "2") (pinfunction "2_2") (pintype "passive"))
      (node (ref "S3") (pin "2") (pinfunction "2_2") (pintype "passive"))
      (node (ref "S30") (pin "2") (pinfunction "2_2") (pintype "passive"))
      (node (ref "S31") (pin "2") (pinfunction "2_2") (pintype "passive"))
      (node (ref "S32") (pin "2") (pinfunction "2_2") (pintype "passive"))
      (node (ref "S33") (pin "2") (pinfunction "2_2") (pintype "passive"))
      (node (ref "S34") (pin "2") (pinfunction "2_2") (pintype "passive"))
      (node (ref "S35") (pin "2") (pinfunction "2_2") (pintype "passive"))
      (node (ref "S36") (pin "2") (pinfunction "2_2") (pintype "passive"))
      (node (ref "S37") (pin "2") (pinfunction "2_2") (pintype "passive"))
      (node (ref "S38") (pin "2") (pinfunction "2_2") (pintype "passive"))
      (node (ref "S39") (pin "2") (pinfunction "2_2") (pintype "passive"))
      (node (ref "S4") (pin "2") (pinfunction "2_2") (pintype "passive"))
      (node (ref "S40") (pin "2") (pinfunction "2_2") (pintype "passive"))
      (node (ref "S41") (pin "2") (pinfunction "2_2") (pintype "passive"))
      (node (ref "S42") (pin "2") (pinfunction "2_2") (pintype "passive"))
      (node (ref "S43") (pin "2") (pinfunction "2_2") (pintype "passive"))
      (node (ref "S44") (pin "2") (pinfunction "2_2") (pintype "passive"))
      (node (ref "S45") (pin "2") (pinfunction "2_2") (pintype "passive"))
      (node (ref "S46") (pin "2") (pinfunction "2_2") (pintype "passive"))
      (node (ref "S47") (pin "2") (pinfunction "2_2") (pintype "passive"))
      (node (ref "S48") (pin "2") (pinfunction "2_2") (pintype "passive"))
      (node (ref "S49") (pin "2") (pinfunction "2_2") (pintype "passive"))
      (node (ref "S5") (pin "2") (pinfunction "2_2") (pintype "passive"))
      (node (ref "S50") (pin "2") (pinfunction "2_2") (pintype "passive"))
      (node (ref "S51") (pin "2") (pinfunction "2_2") (pintype "passive"))
      (node (ref "S52") (pin "2") (pinfunction "2_2") (pintype "passive"))
      (node (ref "S53") (pin "2") (pinfunction "2_2") (pintype "passive"))
      (node (ref "S54") (pin "2") (pinfunction "2_2") (pintype "passive"))
      (node (ref "S55") (pin "2") (pinfunction "2_2") (pintype "passive"))
      (node (ref "S56") (pin "2") (pinfunction "2_2") (pintype "passive"))
      (node (ref "S57") (pin "2") (pinfunction "2_2") (pintype "passive"))
      (node (ref "S58") (pin "2") (pinfunction "2_2") (pintype "passive"))
      (node (ref "S59") (pin "2") (pinfunction "2_2") (pintype "passive"))
      (node (ref "S6") (pin "2") (pinfunction "2_2") (pintype "passive"))
      (node (ref "S60") (pin "2") (pinfunction "2_2") (pintype "passive"))
      (node (ref "S61") (pin "2") (pinfunction "2_2") (pintype "passive"))
      (node (ref "S62") (pin "2") (pinfunction "2_2") (pintype "passive"))
      (node (ref "S63") (pin "2") (pinfunction "2_2") (pintype "passive"))
      (node (ref "S64") (pin "2") (pinfunction "2_2") (pintype "passive"))
      (node (ref "S7") (pin "2") (pinfunction "2_2") (pintype "passive"))
      (node (ref "S8") (pin "2") (pinfunction "2_2") (pintype "passive"))
      (node (ref "S9") (pin "2") (pinfunction "2_2") (pintype "passive"))
    )
    (net (code "192") (name "unconnected-(IC2A-QB-Pad1)") (class "Default")
      (node (ref "IC2") (pin "1") (pinfunction "QB_1") (pintype "tri_state"))
    )
    (net (code "193") (name "unconnected-(IC3A-QB-Pad1)") (class "Default")
      (node (ref "IC3") (pin "1") (pinfunction "QB_1") (pintype "tri_state"))
    )
    (net (code "194") (name "unconnected-(IC4A-QB-Pad1)") (class "Default")
      (node (ref "IC4") (pin "1") (pinfunction "QB_1") (pintype "tri_state"))
    )
    (net (code "195") (name "unconnected-(IC5A-QB-Pad1)") (class "Default")
      (node (ref "IC5") (pin "1") (pinfunction "QB_1") (pintype "tri_state"))
    )
    (net (code "196") (name "unconnected-(IC6A-QB-Pad1)") (class "Default")
      (node (ref "IC6") (pin "1") (pinfunction "QB_1") (pintype "tri_state"))
    )
    (net (code "197") (name "unconnected-(IC7A-QB-Pad1)") (class "Default")
      (node (ref "IC7") (pin "1") (pinfunction "QB_1") (pintype "tri_state"))
    )
    (net (code "198") (name "unconnected-(IC8A-QB-Pad1)") (class "Default")
      (node (ref "IC8") (pin "1") (pinfunction "QB_1") (pintype "tri_state"))
    )
    (net (code "199") (name "unconnected-(IC9A-QB-Pad1)") (class "Default")
      (node (ref "IC9") (pin "1") (pinfunction "QB_1") (pintype "tri_state"))
    )
    (net (code "200") (name "unconnected-(IC10A-QB-Pad1)") (class "Default")
      (node (ref "IC10") (pin "1") (pinfunction "QB_1") (pintype "tri_state"))
    )
    (net (code "201") (name "unconnected-(IC11A-QH*-Pad9)") (class "Default")
      (node (ref "IC11") (pin "9") (pinfunction "QH*_9") (pintype "tri_state"))
    )
    (net (code "202") (name "unconnected-(IC12A-Q6-Pad2)") (class "Default")
      (node (ref "IC12") (pin "2") (pinfunction "Q6_2") (pintype "output"))
    )
    (net (code "203") (name "unconnected-(IC12A-Q7-Pad12)") (class "Default")
      (node (ref "IC12") (pin "12") (pinfunction "Q7_12") (pintype "output"))
    )
    (net (code "204") (name "unconnected-(IC13A-Q6-Pad2)") (class "Default")
      (node (ref "IC13") (pin "2") (pinfunction "Q6_2") (pintype "output"))
    )
    (net (code "205") (name "unconnected-(IC13A-Q7-Pad12)") (class "Default")
      (node (ref "IC13") (pin "12") (pinfunction "Q7_12") (pintype "output"))
    )
    (net (code "206") (name "unconnected-(IC14A-Q6-Pad2)") (class "Default")
      (node (ref "IC14") (pin "2") (pinfunction "Q6_2") (pintype "output"))
    )
    (net (code "207") (name "unconnected-(IC14A-Q7-Pad12)") (class "Default")
      (node (ref "IC14") (pin "12") (pinfunction "Q7_12") (pintype "output"))
    )
    (net (code "208") (name "unconnected-(IC15A-Q6-Pad2)") (class "Default")
      (node (ref "IC15") (pin "2") (pinfunction "Q6_2") (pintype "output"))
    )
    (net (code "209") (name "unconnected-(IC15A-Q7-Pad12)") (class "Default")
      (node (ref "IC15") (pin "12") (pinfunction "Q7_12") (pintype "output"))
    )
    (net (code "210") (name "unconnected-(IC16A-Q6-Pad2)") (class "Default")
      (node (ref "IC16") (pin "2") (pinfunction "Q6_2") (pintype "output"))
    )
    (net (code "211") (name "unconnected-(IC16A-Q7-Pad12)") (class "Default")
      (node (ref "IC16") (pin "12") (pinfunction "Q7_12") (pintype "output"))
    )
    (net (code "212") (name "unconnected-(IC17A-Q6-Pad2)") (class "Default")
      (node (ref "IC17") (pin "2") (pinfunction "Q6_2") (pintype "output"))
    )
    (net (code "213") (name "unconnected-(IC17A-Q7-Pad12)") (class "Default")
      (node (ref "IC17") (pin "12") (pinfunction "Q7_12") (pintype "output"))
    )
    (net (code "214") (name "unconnected-(IC18A-Q6-Pad2)") (class "Default")
      (node (ref "IC18") (pin "2") (pinfunction "Q6_2") (pintype "output"))
    )
    (net (code "215") (name "unconnected-(IC18A-Q7-Pad12)") (class "Default")
      (node (ref "IC18") (pin "12") (pinfunction "Q7_12") (pintype "output"))
    )
    (net (code "216") (name "unconnected-(IC19A-Q6-Pad2)") (class "Default")
      (node (ref "IC19") (pin "2") (pinfunction "Q6_2") (pintype "output"))
    )
    (net (code "217") (name "unconnected-(IC19A-Q7-Pad12)") (class "Default")
      (node (ref "IC19") (pin "12") (pinfunction "Q7_12") (pintype "output"))
    )
    (net (code "218") (name "unconnected-(IC20A-Q6-Pad2)") (class "Default")
      (node (ref "IC20") (pin "2") (pinfunction "Q6_2") (pintype "output"))
    )
    (net (code "219") (name "unconnected-(IC20A-Q7-Pad12)") (class "Default")
      (node (ref "IC20") (pin "12") (pinfunction "Q7_12") (pintype "output"))
    )
    (net (code "220") (name "unconnected-(IC21A-Q6-Pad2)") (class "Default")
      (node (ref "IC21") (pin "2") (pinfunction "Q6_2") (pintype "output"))
    )
    (net (code "221") (name "unconnected-(IC21A-Q7-Pad12)") (class "Default")
      (node (ref "IC21") (pin "12") (pinfunction "Q7_12") (pintype "output"))
    )
    (net (code "222") (name "unconnected-(IC21A-SI-Pad11)") (class "Default")
      (node (ref "IC21") (pin "11") (pinfunction "SI_11") (pintype "input"))
    )
    (net (code "223") (name "unconnected-(JP1-Pad5)") (class "Default")
      (node (ref "JP1") (pin "5") (pinfunction "5_5") (pintype "passive"))
    )
    (net (code "224") (name "unconnected-(JP1-Pad8)") (class "Default")
      (node (ref "JP1") (pin "8") (pinfunction "8_8") (pintype "passive"))
    )
    (net (code "225") (name "unconnected-(JP1-Pad9)") (class "Default")
      (node (ref "JP1") (pin "9") (pinfunction "9_9") (pintype "passive"))
    )
    (net (code "226") (name "unconnected-(LED13-PadA)") (class "Default")
      (node (ref "LED13") (pin "A") (pinfunction "A_A") (pintype "passive"))
    )
    (net (code "227") (name "unconnected-(LED21-PadA)") (class "Default")
      (node (ref "LED21") (pin "A") (pinfunction "A_A") (pintype "passive"))
    )
    (net (code "228") (name "unconnected-(LED29-PadA)") (class "Default")
      (node (ref "LED29") (pin "A") (pinfunction "A_A") (pintype "passive"))
    )
    (net (code "229") (name "unconnected-(LED37-PadA)") (class "Default")
      (node (ref "LED37") (pin "A") (pinfunction "A_A") (pintype "passive"))
    )
    (net (code "230") (name "unconnected-(LED45-PadA)") (class "Default")
      (node (ref "LED45") (pin "A") (pinfunction "A_A") (pintype "passive"))
    )
    (net (code "231") (name "unconnected-(LED53-PadA)") (class "Default")
      (node (ref "LED53") (pin "A") (pinfunction "A_A") (pintype "passive"))
    )
    (net (code "232") (name "unconnected-(LED61-PadA)") (class "Default")
      (node (ref "LED61") (pin "A") (pinfunction "A_A") (pintype "passive"))
    )
    (net (code "233") (name "unconnected-(LED69-PadA)") (class "Default")
      (node (ref "LED69") (pin "A") (pinfunction "A_A") (pintype "passive"))
    )
    (net (code "234") (name "unconnected-(LED77-PadA)") (class "Default")
      (node (ref "LED77") (pin "A") (pinfunction "A_A") (pintype "passive"))
    )
  )
)
